# Schematic.net
KiCad netlist of a schematic drawn in Altium Designer
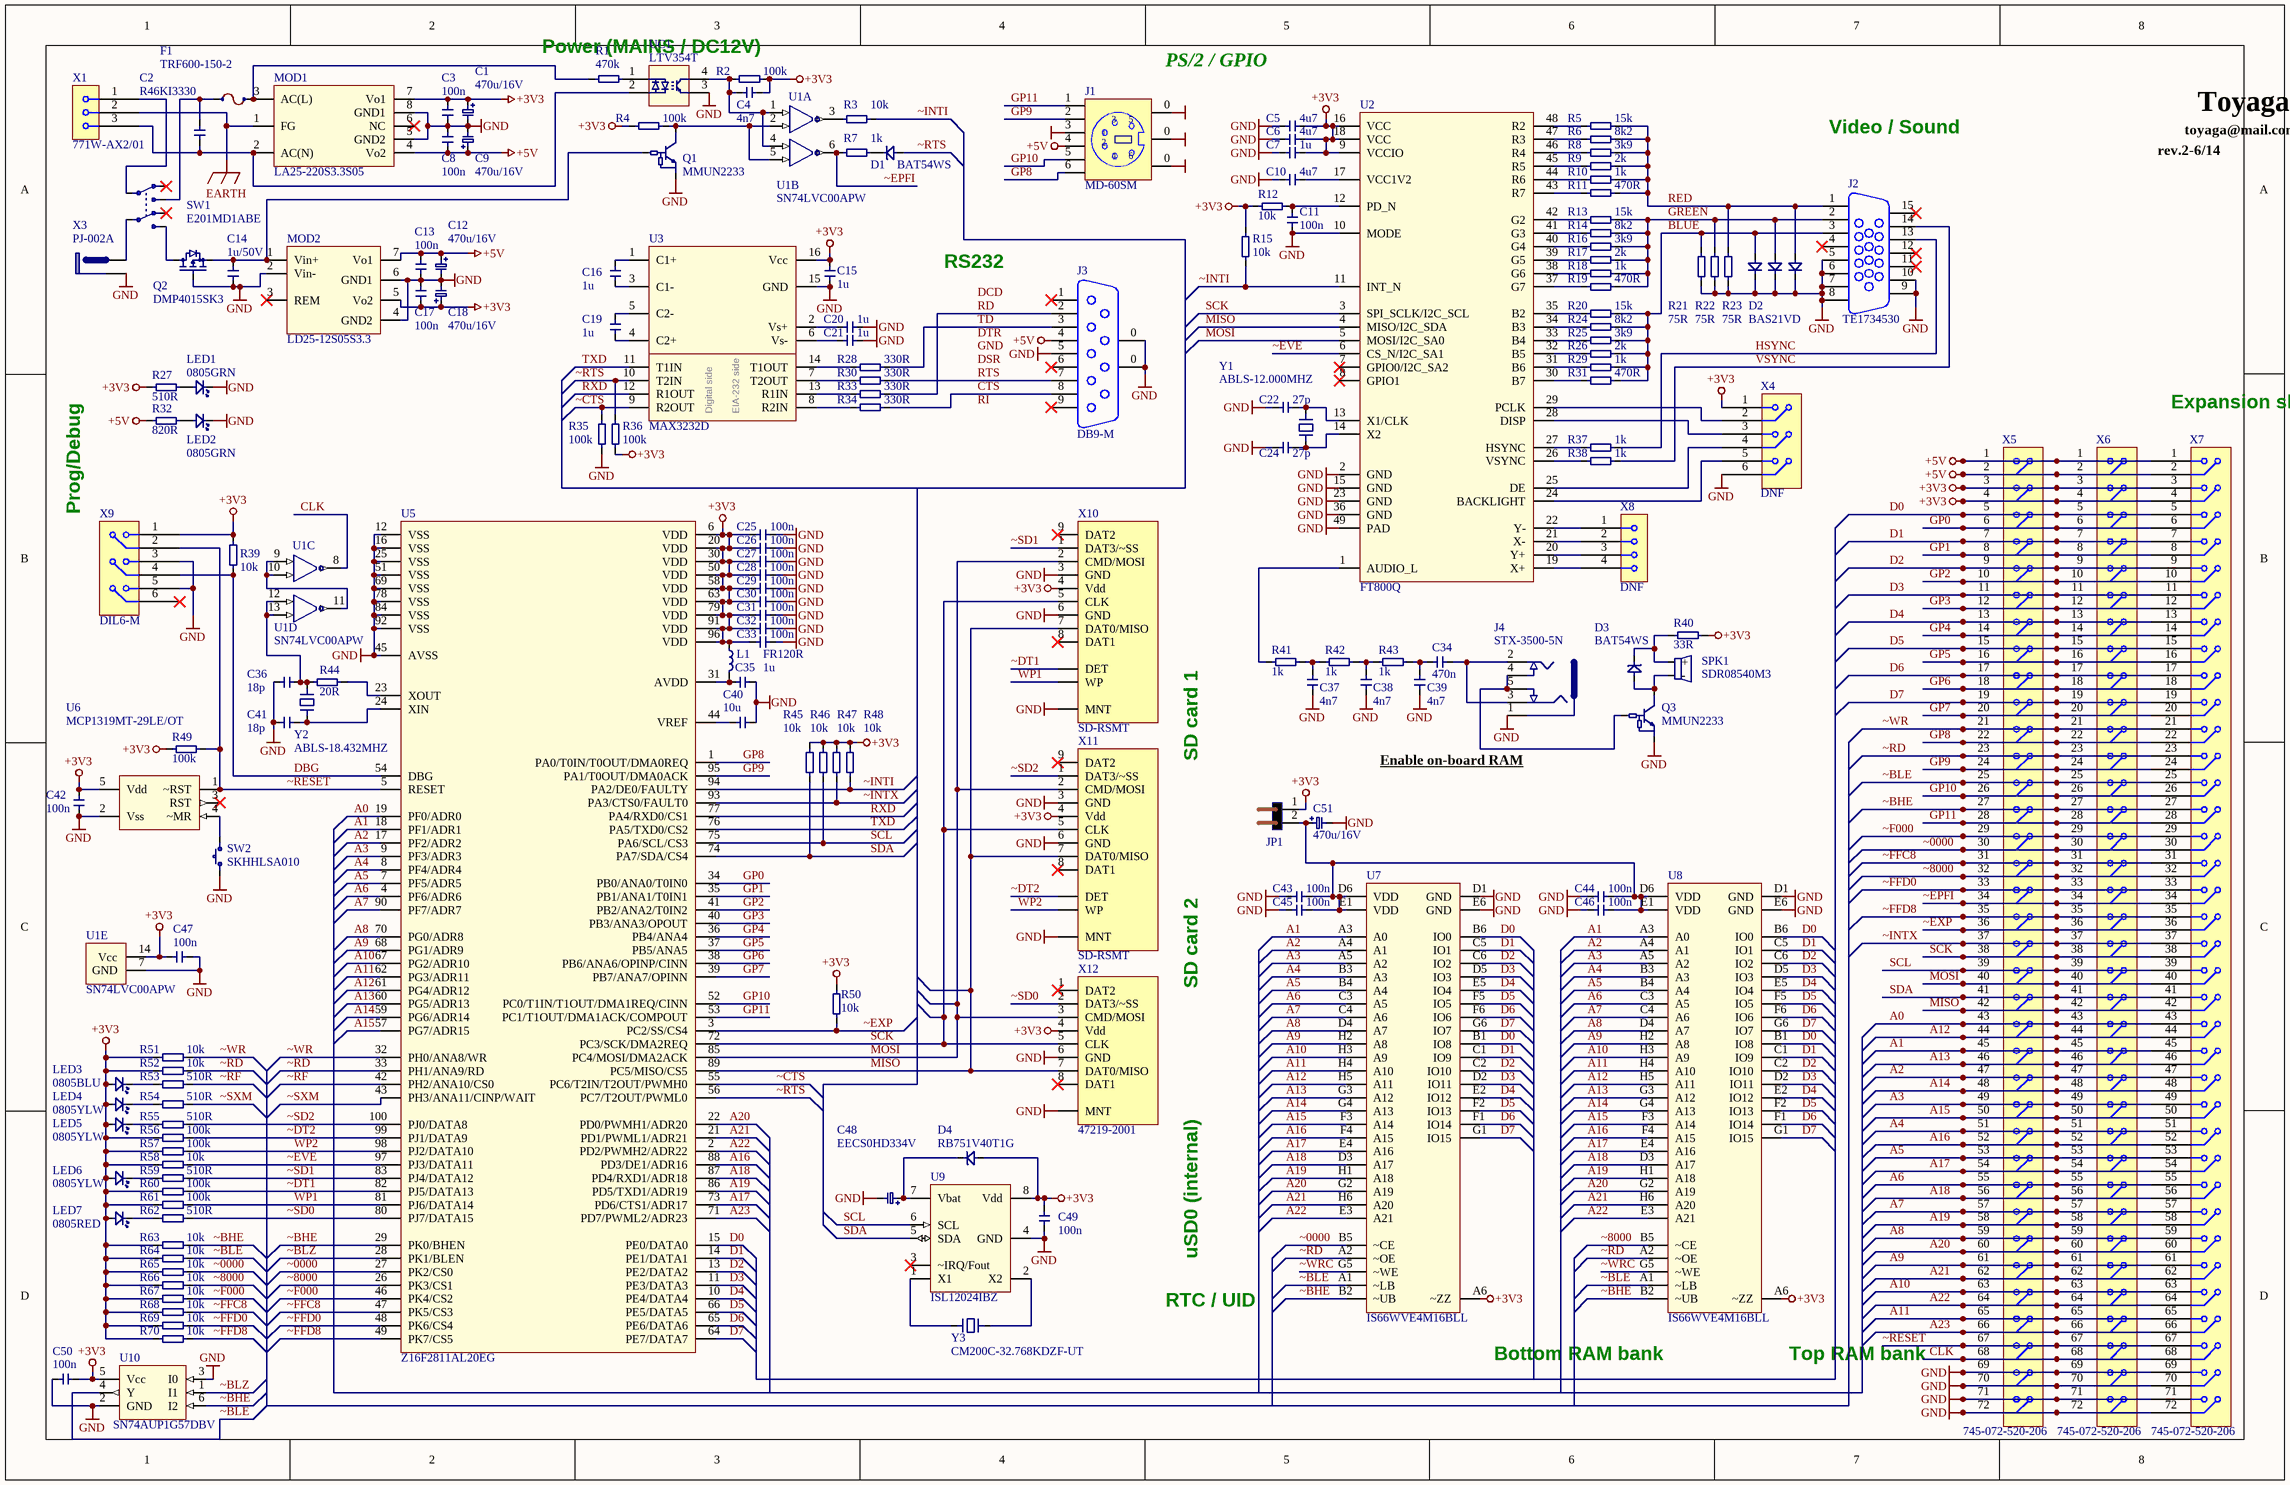
[diagram p0: Schematic.SchDoc]

(export (version "E")
  (design (tool "Eeschema 10.0.6"))
  (components
    (comp (ref "C1")
      (value "470u/16V")
      (footprint "8.5 x 8.5")
      (description "Polar capacitor")
      (libsource (lib "Discretes") (part "Capacitor+"))
    )
    (comp (ref "C2")
      (value "R46KI3330")
      (footprint "X2_15MM")
      (description "Capacitor")
      (libsource (lib "Discretes") (part "Capacitor"))
    )
    (comp (ref "C3")
      (value "100n")
      (footprint "_0805")
      (description "Capacitor")
      (libsource (lib "Discretes") (part "Capacitor"))
    )
    (comp (ref "C4")
      (value "4n7")
      (footprint "_0805")
      (description "Capacitor")
      (libsource (lib "Discretes") (part "Capacitor"))
    )
    (comp (ref "C5")
      (value "4u7")
      (footprint "_0805")
      (description "Capacitor")
      (libsource (lib "Discretes") (part "Capacitor"))
    )
    (comp (ref "C6")
      (value "4u7")
      (footprint "_0805")
      (description "Capacitor")
      (libsource (lib "Discretes") (part "Capacitor"))
    )
    (comp (ref "C7")
      (value "1u")
      (footprint "_0805")
      (description "Capacitor")
      (libsource (lib "Discretes") (part "Capacitor"))
    )
    (comp (ref "C8")
      (value "100n")
      (footprint "_0805")
      (description "Capacitor")
      (libsource (lib "Discretes") (part "Capacitor"))
    )
    (comp (ref "C9")
      (value "470u/16V")
      (footprint "8.5 x 8.5")
      (description "Polar capacitor")
      (libsource (lib "Discretes") (part "Capacitor+"))
    )
    (comp (ref "C10")
      (value "4u7")
      (footprint "_0805")
      (description "Capacitor")
      (libsource (lib "Discretes") (part "Capacitor"))
    )
    (comp (ref "C11")
      (value "100n")
      (footprint "_0805")
      (description "Capacitor")
      (libsource (lib "Discretes") (part "Capacitor"))
    )
    (comp (ref "C12")
      (value "470u/16V")
      (footprint "8.5 x 8.5")
      (description "Polar capacitor")
      (libsource (lib "Discretes") (part "Capacitor+"))
    )
    (comp (ref "C13")
      (value "100n")
      (footprint "_0805")
      (description "Capacitor")
      (libsource (lib "Discretes") (part "Capacitor"))
    )
    (comp (ref "C14")
      (value "1u/50V")
      (footprint "_1206")
      (description "Capacitor")
      (libsource (lib "Discretes") (part "Capacitor"))
    )
    (comp (ref "C15")
      (value "1u")
      (footprint "_0805")
      (description "Capacitor")
      (libsource (lib "Discretes") (part "Capacitor"))
    )
    (comp (ref "C16")
      (value "1u")
      (footprint "_0805")
      (description "Capacitor")
      (libsource (lib "Discretes") (part "Capacitor"))
    )
    (comp (ref "C17")
      (value "100n")
      (footprint "_0805")
      (description "Capacitor")
      (libsource (lib "Discretes") (part "Capacitor"))
    )
    (comp (ref "C18")
      (value "470u/16V")
      (footprint "8.5 x 8.5")
      (description "Polar capacitor")
      (libsource (lib "Discretes") (part "Capacitor+"))
    )
    (comp (ref "C19")
      (value "1u")
      (footprint "_0805")
      (description "Capacitor")
      (libsource (lib "Discretes") (part "Capacitor"))
    )
    (comp (ref "C20")
      (value "1u")
      (footprint "_0805")
      (description "Capacitor")
      (libsource (lib "Discretes") (part "Capacitor"))
    )
    (comp (ref "C21")
      (value "1u")
      (footprint "_0805")
      (description "Capacitor")
      (libsource (lib "Discretes") (part "Capacitor"))
    )
    (comp (ref "C22")
      (value "27p")
      (footprint "_0805")
      (description "Capacitor")
      (libsource (lib "Discretes") (part "Capacitor"))
    )
    (comp (ref "C24")
      (value "27p")
      (footprint "_0805")
      (description "Capacitor")
      (libsource (lib "Discretes") (part "Capacitor"))
    )
    (comp (ref "C25")
      (value "100n")
      (footprint "_0805")
      (description "Capacitor")
      (libsource (lib "Discretes") (part "Capacitor"))
    )
    (comp (ref "C26")
      (value "100n")
      (footprint "_0805")
      (description "Capacitor")
      (libsource (lib "Discretes") (part "Capacitor"))
    )
    (comp (ref "C27")
      (value "100n")
      (footprint "_0805")
      (description "Capacitor")
      (libsource (lib "Discretes") (part "Capacitor"))
    )
    (comp (ref "C28")
      (value "100n")
      (footprint "_0805")
      (description "Capacitor")
      (libsource (lib "Discretes") (part "Capacitor"))
    )
    (comp (ref "C29")
      (value "100n")
      (footprint "_0805")
      (description "Capacitor")
      (libsource (lib "Discretes") (part "Capacitor"))
    )
    (comp (ref "C30")
      (value "100n")
      (footprint "_0805")
      (description "Capacitor")
      (libsource (lib "Discretes") (part "Capacitor"))
    )
    (comp (ref "C31")
      (value "100n")
      (footprint "_0805")
      (description "Capacitor")
      (libsource (lib "Discretes") (part "Capacitor"))
    )
    (comp (ref "C32")
      (value "100n")
      (footprint "_0805")
      (description "Capacitor")
      (libsource (lib "Discretes") (part "Capacitor"))
    )
    (comp (ref "C33")
      (value "100n")
      (footprint "_0805")
      (description "Capacitor")
      (libsource (lib "Discretes") (part "Capacitor"))
    )
    (comp (ref "C34")
      (value "470n")
      (footprint "_0805")
      (description "Capacitor")
      (libsource (lib "Discretes") (part "Capacitor"))
    )
    (comp (ref "C35")
      (value "1u")
      (footprint "_0805")
      (description "Capacitor")
      (libsource (lib "Discretes") (part "Capacitor"))
    )
    (comp (ref "C36")
      (value "18p")
      (footprint "_0805")
      (description "Capacitor")
      (libsource (lib "Discretes") (part "Capacitor"))
    )
    (comp (ref "C37")
      (value "4n7")
      (footprint "_0805")
      (description "Capacitor")
      (libsource (lib "Discretes") (part "Capacitor"))
    )
    (comp (ref "C38")
      (value "4n7")
      (footprint "_0805")
      (description "Capacitor")
      (libsource (lib "Discretes") (part "Capacitor"))
    )
    (comp (ref "C39")
      (value "4n7")
      (footprint "_0805")
      (description "Capacitor")
      (libsource (lib "Discretes") (part "Capacitor"))
    )
    (comp (ref "C40")
      (value "10u")
      (footprint "_0805")
      (description "Capacitor")
      (libsource (lib "Discretes") (part "Capacitor"))
    )
    (comp (ref "C41")
      (value "18p")
      (footprint "_0805")
      (description "Capacitor")
      (libsource (lib "Discretes") (part "Capacitor"))
    )
    (comp (ref "C42")
      (value "100n")
      (footprint "_0805")
      (description "Capacitor")
      (libsource (lib "Discretes") (part "Capacitor"))
    )
    (comp (ref "C43")
      (value "100n")
      (footprint "_0805")
      (description "Capacitor")
      (libsource (lib "Discretes") (part "Capacitor"))
    )
    (comp (ref "C44")
      (value "100n")
      (footprint "_0805")
      (description "Capacitor")
      (libsource (lib "Discretes") (part "Capacitor"))
    )
    (comp (ref "C45")
      (value "100n")
      (footprint "_0805")
      (description "Capacitor")
      (libsource (lib "Discretes") (part "Capacitor"))
    )
    (comp (ref "C46")
      (value "100n")
      (footprint "_0805")
      (description "Capacitor")
      (libsource (lib "Discretes") (part "Capacitor"))
    )
    (comp (ref "C47")
      (value "100n")
      (footprint "_0805")
      (description "Capacitor")
      (libsource (lib "Discretes") (part "Capacitor"))
    )
    (comp (ref "C48")
      (value "EECS0HD334V")
      (footprint "D10.5 x L5.5")
      (description "Polar capacitor")
      (libsource (lib "Discretes") (part "Capacitor+"))
    )
    (comp (ref "C49")
      (value "100n")
      (footprint "_0805")
      (description "Capacitor")
      (libsource (lib "Discretes") (part "Capacitor"))
    )
    (comp (ref "C50")
      (value "100n")
      (footprint "_0805")
      (description "Capacitor")
      (libsource (lib "Discretes") (part "Capacitor"))
    )
    (comp (ref "C51")
      (value "470u/16V")
      (footprint "8.5 x 8.5")
      (description "Polar capacitor")
      (libsource (lib "Discretes") (part "Capacitor+"))
    )
    (comp (ref "D1")
      (value "BAT54WS")
      (footprint "SOD-323 (MicroMELF)")
      (description "Schottky diode")
      (libsource (lib "Discretes") (part "Diode Schottky"))
    )
    (comp (ref "D2")
      (value "BAS21VD")
      (footprint "SOT23-6")
      (description "Diode (triple)")
      (libsource (lib "Discretes") (part "Diode Triple"))
    )
    (comp (ref "D3")
      (value "BAT54WS")
      (footprint "SOD-323 (MicroMELF)")
      (description "Schottky diode")
      (libsource (lib "Discretes") (part "Diode Schottky"))
    )
    (comp (ref "D4")
      (value "RB751V40T1G")
      (footprint "SOD-323 (MicroMELF)")
      (description "Schottky diode")
      (libsource (lib "Discretes") (part "Diode Schottky"))
    )
    (comp (ref "F1")
      (value "TRF600-150-2")
      (footprint "Fuse 5.1mm pitch")
      (libsource (lib "Discretes") (part "Fuse Resettable"))
    )
    (comp (ref "J1")
      (value "MD-60SM")
      (footprint "MD-60SM")
      (description "6-pin mini-DIN connector (female) PS/2")
      (libsource (lib "Connectors") (part "MD-60SM"))
    )
    (comp (ref "J2")
      (value "TE1734530")
      (footprint "DB15F R/A VGA")
      (description "DB15 (3 rows) connector R/A")
      (libsource (lib "Connectors") (part "DB15 (3 rows)"))
    )
    (comp (ref "J3")
      (value "DB9-M")
      (footprint "DB9M R/A")
      (description "DB9 connector")
      (libsource (lib "Connectors") (part "DB9"))
    )
    (comp (ref "J4")
      (value "STX-3500-5N")
      (footprint "STX-3500")
      (description "Phono Jack (stereo)")
      (libsource (lib "Connectors") (part "Phono Jack Stereo (switchless)"))
    )
    (comp (ref "JP1")
      (value "SIL2-M")
      (footprint "2011-1X02S")
      (description "2.54mm square pin header/jumper")
      (libsource (lib "Connectors") (part "Jumper 2"))
    )
    (comp (ref "L1")
      (value "FR120R")
      (footprint "_0805")
      (description "Inductor")
      (libsource (lib "Discretes") (part "Inductor"))
    )
    (comp (ref "LED1")
      (value "0805GRN")
      (footprint "_0805+")
      (description "Light Emitting Diode")
      (libsource (lib "Discretes") (part "LED"))
    )
    (comp (ref "LED2")
      (value "0805GRN")
      (footprint "_0805+")
      (description "Light Emitting Diode")
      (libsource (lib "Discretes") (part "LED"))
    )
    (comp (ref "LED3")
      (value "0805BLU")
      (footprint "_0805+")
      (description "Light Emitting Diode")
      (libsource (lib "Discretes") (part "LED"))
    )
    (comp (ref "LED4")
      (value "0805YLW")
      (footprint "_0805+")
      (description "Light Emitting Diode")
      (libsource (lib "Discretes") (part "LED"))
    )
    (comp (ref "LED5")
      (value "0805YLW")
      (footprint "_0805+")
      (description "Light Emitting Diode")
      (libsource (lib "Discretes") (part "LED"))
    )
    (comp (ref "LED6")
      (value "0805YLW")
      (footprint "_0805+")
      (description "Light Emitting Diode")
      (libsource (lib "Discretes") (part "LED"))
    )
    (comp (ref "LED7")
      (value "0805RED")
      (footprint "_0805+")
      (description "Light Emitting Diode")
      (libsource (lib "Discretes") (part "LED"))
    )
    (comp (ref "MOD1")
      (value "LA25-220S3.3S05")
      (footprint "ECCO AC-DC (70x48)")
      (description "Miniature AC/DC module")
      (fields (field (name "MANUFACTURER") "ECCO"))
      (libsource (lib "16Z") (part "ECCO AC-DC dual"))
    )
    (comp (ref "MOD2")
      (value "LD25-12S05S3.3")
      (footprint "DC-DC (50.8x50.8)")
      (description "DC-DC converter isolated output with common ground and control")
      (libsource (lib "16Z") (part "ECCO DC-DC dual"))
    )
    (comp (ref "Q1")
      (value "MMUN2233")
      (footprint "SOT23-3")
      (description "NPN biased bipolar transistor")
      (libsource (lib "Discretes") (part "NPN BIASED"))
    )
    (comp (ref "Q2")
      (value "DMP4015SK3")
      (footprint "TO252-3N")
      (description "P-channel FET transistor")
      (libsource (lib "Discretes") (part "P-FET"))
    )
    (comp (ref "Q3")
      (value "MMUN2233")
      (footprint "SOT23-3")
      (description "NPN biased bipolar transistor")
      (libsource (lib "Discretes") (part "NPN BIASED"))
    )
    (comp (ref "R1")
      (value "470k")
      (footprint "_0805")
      (description "Resistor")
      (libsource (lib "") (part "Resistor_1"))
    )
    (comp (ref "R2")
      (value "100k")
      (footprint "_0805")
      (description "Resistor")
      (libsource (lib "") (part "Resistor_1"))
    )
    (comp (ref "R3")
      (value "10k")
      (footprint "_0805")
      (description "Resistor")
      (libsource (lib "") (part "Resistor_1"))
    )
    (comp (ref "R4")
      (value "100k")
      (footprint "_0805")
      (description "Resistor")
      (libsource (lib "") (part "Resistor_1"))
    )
    (comp (ref "R5")
      (value "15k")
      (footprint "_0805")
      (description "Resistor")
      (libsource (lib "") (part "Resistor_1"))
    )
    (comp (ref "R6")
      (value "8k2")
      (footprint "_0805")
      (description "Resistor")
      (libsource (lib "") (part "Resistor_1"))
    )
    (comp (ref "R7")
      (value "1k")
      (footprint "_0805")
      (description "Resistor")
      (libsource (lib "") (part "Resistor_1"))
    )
    (comp (ref "R8")
      (value "3k9")
      (footprint "_0805")
      (description "Resistor")
      (libsource (lib "") (part "Resistor_1"))
    )
    (comp (ref "R9")
      (value "2k")
      (footprint "_0805")
      (description "Resistor")
      (libsource (lib "") (part "Resistor_1"))
    )
    (comp (ref "R10")
      (value "1k")
      (footprint "_0805")
      (description "Resistor")
      (libsource (lib "") (part "Resistor_1"))
    )
    (comp (ref "R11")
      (value "470R")
      (footprint "_0805")
      (description "Resistor")
      (libsource (lib "") (part "Resistor_1"))
    )
    (comp (ref "R12")
      (value "10k")
      (footprint "_0805")
      (description "Resistor")
      (libsource (lib "") (part "Resistor_1"))
    )
    (comp (ref "R13")
      (value "15k")
      (footprint "_0805")
      (description "Resistor")
      (libsource (lib "") (part "Resistor_1"))
    )
    (comp (ref "R14")
      (value "8k2")
      (footprint "_0805")
      (description "Resistor")
      (libsource (lib "") (part "Resistor_1"))
    )
    (comp (ref "R15")
      (value "10k")
      (footprint "_0805")
      (description "Resistor")
      (libsource (lib "") (part "Resistor_2"))
    )
    (comp (ref "R16")
      (value "3k9")
      (footprint "_0805")
      (description "Resistor")
      (libsource (lib "") (part "Resistor_1"))
    )
    (comp (ref "R17")
      (value "2k")
      (footprint "_0805")
      (description "Resistor")
      (libsource (lib "") (part "Resistor_1"))
    )
    (comp (ref "R18")
      (value "1k")
      (footprint "_0805")
      (description "Resistor")
      (libsource (lib "") (part "Resistor_1"))
    )
    (comp (ref "R19")
      (value "470R")
      (footprint "_0805")
      (description "Resistor")
      (libsource (lib "") (part "Resistor_1"))
    )
    (comp (ref "R20")
      (value "15k")
      (footprint "_0805")
      (description "Resistor")
      (libsource (lib "") (part "Resistor_1"))
    )
    (comp (ref "R21")
      (value "75R")
      (footprint "_0805")
      (description "Resistor")
      (libsource (lib "") (part "Resistor_2"))
    )
    (comp (ref "R22")
      (value "75R")
      (footprint "_0805")
      (description "Resistor")
      (libsource (lib "") (part "Resistor_2"))
    )
    (comp (ref "R23")
      (value "75R")
      (footprint "_0805")
      (description "Resistor")
      (libsource (lib "") (part "Resistor_2"))
    )
    (comp (ref "R24")
      (value "8k2")
      (footprint "_0805")
      (description "Resistor")
      (libsource (lib "") (part "Resistor_1"))
    )
    (comp (ref "R25")
      (value "3k9")
      (footprint "_0805")
      (description "Resistor")
      (libsource (lib "") (part "Resistor_1"))
    )
    (comp (ref "R26")
      (value "2k")
      (footprint "_0805")
      (description "Resistor")
      (libsource (lib "") (part "Resistor_1"))
    )
    (comp (ref "R27")
      (value "510R")
      (footprint "_0805")
      (description "Resistor")
      (libsource (lib "Discretes") (part "Resistor"))
    )
    (comp (ref "R28")
      (value "330R")
      (footprint "_0805")
      (description "Resistor")
      (libsource (lib "") (part "Resistor_1"))
    )
    (comp (ref "R29")
      (value "1k")
      (footprint "_0805")
      (description "Resistor")
      (libsource (lib "") (part "Resistor_1"))
    )
    (comp (ref "R30")
      (value "330R")
      (footprint "_0805")
      (description "Resistor")
      (libsource (lib "") (part "Resistor_1"))
    )
    (comp (ref "R31")
      (value "470R")
      (footprint "_0805")
      (description "Resistor")
      (libsource (lib "") (part "Resistor_1"))
    )
    (comp (ref "R32")
      (value "820R")
      (footprint "_0805")
      (description "Resistor")
      (libsource (lib "Discretes") (part "Resistor"))
    )
    (comp (ref "R33")
      (value "330R")
      (footprint "_0805")
      (description "Resistor")
      (libsource (lib "") (part "Resistor_1"))
    )
    (comp (ref "R34")
      (value "330R")
      (footprint "_0805")
      (description "Resistor")
      (libsource (lib "") (part "Resistor_1"))
    )
    (comp (ref "R35")
      (value "100k")
      (footprint "_0805")
      (description "Resistor")
      (libsource (lib "") (part "Resistor_2"))
    )
    (comp (ref "R36")
      (value "100k")
      (footprint "_0805")
      (description "Resistor")
      (libsource (lib "") (part "Resistor_2"))
    )
    (comp (ref "R37")
      (value "1k")
      (footprint "_0805")
      (description "Resistor")
      (libsource (lib "") (part "Resistor_1"))
    )
    (comp (ref "R38")
      (value "1k")
      (footprint "_0805")
      (description "Resistor")
      (libsource (lib "") (part "Resistor_1"))
    )
    (comp (ref "R39")
      (value "10k")
      (footprint "_0805")
      (description "Resistor")
      (libsource (lib "") (part "Resistor_3"))
    )
    (comp (ref "R40")
      (value "33R")
      (footprint "_0805")
      (description "Resistor")
      (libsource (lib "") (part "Resistor_1"))
    )
    (comp (ref "R41")
      (value "1k")
      (footprint "_0805")
      (description "Resistor")
      (libsource (lib "") (part "Resistor_1"))
    )
    (comp (ref "R42")
      (value "1k")
      (footprint "_0805")
      (description "Resistor")
      (libsource (lib "") (part "Resistor_1"))
    )
    (comp (ref "R43")
      (value "1k")
      (footprint "_0805")
      (description "Resistor")
      (libsource (lib "") (part "Resistor_1"))
    )
    (comp (ref "R44")
      (value "20R")
      (footprint "_0805")
      (description "Resistor")
      (libsource (lib "Discretes") (part "Resistor"))
    )
    (comp (ref "R45")
      (value "10k")
      (footprint "_0805")
      (description "Resistor")
      (libsource (lib "") (part "Resistor_2"))
    )
    (comp (ref "R46")
      (value "10k")
      (footprint "_0805")
      (description "Resistor")
      (libsource (lib "") (part "Resistor_2"))
    )
    (comp (ref "R47")
      (value "10k")
      (footprint "_0805")
      (description "Resistor")
      (libsource (lib "") (part "Resistor_2"))
    )
    (comp (ref "R48")
      (value "10k")
      (footprint "_0805")
      (description "Resistor")
      (libsource (lib "") (part "Resistor_2"))
    )
    (comp (ref "R49")
      (value "100k")
      (footprint "_0805")
      (description "Resistor")
      (libsource (lib "Discretes") (part "Resistor"))
    )
    (comp (ref "R50")
      (value "10k")
      (footprint "_0805")
      (description "Resistor")
      (libsource (lib "") (part "Resistor_2"))
    )
    (comp (ref "R51")
      (value "10k")
      (footprint "_0805")
      (description "Resistor")
      (libsource (lib "Discretes") (part "Resistor"))
    )
    (comp (ref "R52")
      (value "10k")
      (footprint "_0805")
      (description "Resistor")
      (libsource (lib "Discretes") (part "Resistor"))
    )
    (comp (ref "R53")
      (value "510R")
      (footprint "_0805")
      (description "Resistor")
      (libsource (lib "Discretes") (part "Resistor"))
    )
    (comp (ref "R54")
      (value "510R")
      (footprint "_0805")
      (description "Resistor")
      (libsource (lib "Discretes") (part "Resistor"))
    )
    (comp (ref "R55")
      (value "510R")
      (footprint "_0805")
      (description "Resistor")
      (libsource (lib "Discretes") (part "Resistor"))
    )
    (comp (ref "R56")
      (value "100k")
      (footprint "_0805")
      (description "Resistor")
      (libsource (lib "Discretes") (part "Resistor"))
    )
    (comp (ref "R57")
      (value "100k")
      (footprint "_0805")
      (description "Resistor")
      (libsource (lib "Discretes") (part "Resistor"))
    )
    (comp (ref "R58")
      (value "10k")
      (footprint "_0805")
      (description "Resistor")
      (libsource (lib "Discretes") (part "Resistor"))
    )
    (comp (ref "R59")
      (value "510R")
      (footprint "_0805")
      (description "Resistor")
      (libsource (lib "Discretes") (part "Resistor"))
    )
    (comp (ref "R60")
      (value "100k")
      (footprint "_0805")
      (description "Resistor")
      (libsource (lib "Discretes") (part "Resistor"))
    )
    (comp (ref "R61")
      (value "100k")
      (footprint "_0805")
      (description "Resistor")
      (libsource (lib "Discretes") (part "Resistor"))
    )
    (comp (ref "R62")
      (value "510R")
      (footprint "_0805")
      (description "Resistor")
      (libsource (lib "Discretes") (part "Resistor"))
    )
    (comp (ref "R63")
      (value "10k")
      (footprint "_0805")
      (description "Resistor")
      (libsource (lib "Discretes") (part "Resistor"))
    )
    (comp (ref "R64")
      (value "10k")
      (footprint "_0805")
      (description "Resistor")
      (libsource (lib "Discretes") (part "Resistor"))
    )
    (comp (ref "R65")
      (value "10k")
      (footprint "_0805")
      (description "Resistor")
      (libsource (lib "Discretes") (part "Resistor"))
    )
    (comp (ref "R66")
      (value "10k")
      (footprint "_0805")
      (description "Resistor")
      (libsource (lib "Discretes") (part "Resistor"))
    )
    (comp (ref "R67")
      (value "10k")
      (footprint "_0805")
      (description "Resistor")
      (libsource (lib "Discretes") (part "Resistor"))
    )
    (comp (ref "R68")
      (value "10k")
      (footprint "_0805")
      (description "Resistor")
      (libsource (lib "Discretes") (part "Resistor"))
    )
    (comp (ref "R69")
      (value "10k")
      (footprint "_0805")
      (description "Resistor")
      (libsource (lib "Discretes") (part "Resistor"))
    )
    (comp (ref "R70")
      (value "10k")
      (footprint "_0805")
      (description "Resistor")
      (libsource (lib "Discretes") (part "Resistor"))
    )
    (comp (ref "SPK1")
      (value "SDR08540M3")
      (footprint "SDR08540M3-01")
      (description "Speaker/Buzzer")
      (libsource (lib "Discretes") (part "Speaker"))
    )
    (comp (ref "SW1")
      (value "E201MD1ABE")
      (footprint "E201MD1ABE")
      (description "Switch")
      (libsource (lib "Switches") (part "Switch DPDT"))
    )
    (comp (ref "SW2")
      (value "SKHHLSA010")
      (footprint "SKHH-HORIZONTAL")
      (description "Switch, Momentary, Normal Open")
      (libsource (lib "Switches") (part "Switch MNO SPST"))
    )
    (comp (ref "U1")
      (value "SN74LVC00APW")
      (footprint "TSOP65P640-14N")
      (description "Quad NAND")
      (libsource (lib "IC Logic") (part "74xxx00"))
    )
    (comp (ref "U2")
      (value "FT800Q")
      (footprint "QFN50P700X700-48W2N")
      (description "Embedded Video Engine")
      (fields (field (name "MANUFACTURER") "FTDI"))
      (libsource (lib "IC Audio and Video") (part "FT800Q"))
    )
    (comp (ref "U3")
      (value "MAX3232D")
      (footprint "SOIC16")
      (description "Dual EIA-232 drivers")
      (fields (field (name "MANUFACTURER") "TI (and others)"))
      (libsource (lib "IC Interface") (part "MAX232"))
    )
    (comp (ref "U5")
      (value "Z16F2811AL20EG")
      (footprint "LQFP100")
      (description "16-bit microcontroller/microprocessor")
      (fields (field (name "MANUFACTURER") "Zilog"))
      (libsource (lib "IC Microcontrollers and Processors") (part "Z16F (QFP100)"))
    )
    (comp (ref "U6")
      (value "MCP1319MT-29LE/OT")
      (footprint "SOT23-5")
      (description "Voltage Supervisor")
      (fields (field (name "MANUFACTURER") "Microchip"))
      (libsource (lib "IC Other Functions") (part "MCP1319"))
    )
    (comp (ref "U7")
      (value "IS66WVE4M16BLL")
      (footprint "BGA75P6X8-48")
      (description "4M x 16 high speed asynchronous pseudostatic RAM")
      (libsource (lib "IC Other Functions") (part "IS66WVE4M16 BGA"))
    )
    (comp (ref "U8")
      (value "IS66WVE4M16BLL")
      (footprint "BGA75P6X8-48")
      (description "4M x 16 high speed asynchronous pseudostatic RAM")
      (libsource (lib "IC Other Functions") (part "IS66WVE4M16 BGA"))
    )
    (comp (ref "U9")
      (value "ISL12024IBZ")
      (footprint "SOIC8")
      (description "Real-Time Clock/Calendar with Embedded  Unique ID")
      (fields (field (name "MANUFACTURER") "Intersil"))
      (libsource (lib "IC Other Functions") (part "ISL12024"))
    )
    (comp (ref "U10")
      (value "SN74AUP1G57DBV")
      (footprint "SOT23-6")
      (description "Universal logic element")
      (fields (field (name "MANUFACTURER") "Texas Instruments"))
      (libsource (lib "IC Logic") (part "SN74AUP1G57"))
    )
    (comp (ref "UC1")
      (value "LTV354T")
      (footprint "SO4")
      (description "Optocoupler AC")
      (libsource (lib "Discretes") (part "OPTO AC"))
    )
    (comp (ref "X1")
      (value "771W-AX2/01")
      (footprint "771W-AX2/01")
      (description "Single row, 3-way connector")
      (libsource (lib "Connectors") (part "Connector 1x3"))
    )
    (comp (ref "X3")
      (value "PJ-002A")
      (footprint "KLD-0202")
      (description "Power Jack 2.1mm or 2.5mm")
      (libsource (lib "Connectors") (part "Power Jack 2.5"))
    )
    (comp (ref "X4")
      (value "DNF")
      (footprint "2011-2X03S")
      (description "Dual row, 6-way connector")
      (libsource (lib "Connectors") (part "Connector 2x3"))
    )
    (comp (ref "X5")
      (value "745-072-520-206")
      (footprint "745-072-520-206")
      (description "Dual row, 72-way connector")
      (libsource (lib "Connectors") (part "Connector 2x36"))
    )
    (comp (ref "X6")
      (value "745-072-520-206")
      (footprint "745-072-520-206")
      (description "Dual row, 72-way connector")
      (libsource (lib "Connectors") (part "Connector 2x36"))
    )
    (comp (ref "X7")
      (value "745-072-520-206")
      (footprint "745-072-520-206")
      (description "Dual row, 72-way connector")
      (libsource (lib "Connectors") (part "Connector 2x36"))
    )
    (comp (ref "X8")
      (value "DNF")
      (footprint "2011-1X04S")
      (description "Single row, 4-way connector")
      (libsource (lib "Connectors") (part "Connector 1x4"))
    )
    (comp (ref "X9")
      (value "DIL6-M")
      (footprint "2011-2X03S")
      (description "Dual row, 6-way connector")
      (libsource (lib "") (part "Connector 2x3_1"))
    )
    (comp (ref "X10")
      (value "SD-RSMT")
      (footprint "SD-RSMT")
      (description "SD card connector")
      (libsource (lib "Connectors") (part "SD (w/ card detect and WP)"))
    )
    (comp (ref "X11")
      (value "SD-RSMT")
      (footprint "SD-RSMT")
      (description "SD card connector")
      (libsource (lib "Connectors") (part "SD (w/ card detect and WP)"))
    )
    (comp (ref "X12")
      (value "47219-2001")
      (footprint "MOLEX_47219-2001")
      (description "microSD card connector")
      (libsource (lib "Connectors") (part "microSD"))
    )
    (comp (ref "Y1")
      (value "ABLS-12.000MHZ")
      (footprint "HC49/SMT")
      (description "Crystal Resonator")
      (libsource (lib "Discretes") (part "Crystal"))
    )
    (comp (ref "Y2")
      (value "ABLS-18.432MHZ")
      (footprint "HC49/SMT")
      (description "Crystal Resonator")
      (libsource (lib "Discretes") (part "Crystal"))
    )
    (comp (ref "Y3")
      (value "CM200C-32.768KDZF-UT")
      (footprint "Crystal 79X37 (4)")
      (description "Crystal Resonator")
      (libsource (lib "") (part "Crystal_1"))
    )
  )
  (nets
    (net (code "1") (name "+3V3") (class "Default")
      (node (ref "C1") (pin "1") (pintype "passive"))
      (node (ref "C15") (pin "1") (pintype "passive"))
      (node (ref "C17") (pin "2") (pintype "passive"))
      (node (ref "C18") (pin "1") (pintype "passive"))
      (node (ref "C25") (pin "2") (pintype "passive"))
      (node (ref "C26") (pin "2") (pintype "passive"))
      (node (ref "C27") (pin "2") (pintype "passive"))
      (node (ref "C28") (pin "2") (pintype "passive"))
      (node (ref "C29") (pin "2") (pintype "passive"))
      (node (ref "C3") (pin "2") (pintype "passive"))
      (node (ref "C30") (pin "2") (pintype "passive"))
      (node (ref "C31") (pin "2") (pintype "passive"))
      (node (ref "C32") (pin "2") (pintype "passive"))
      (node (ref "C33") (pin "2") (pintype "passive"))
      (node (ref "C4") (pin "2") (pintype "passive"))
      (node (ref "C42") (pin "1") (pintype "passive"))
      (node (ref "C47") (pin "1") (pintype "passive"))
      (node (ref "C49") (pin "1") (pintype "passive"))
      (node (ref "C5") (pin "1") (pintype "passive"))
      (node (ref "C50") (pin "2") (pintype "passive"))
      (node (ref "C6") (pin "1") (pintype "passive"))
      (node (ref "C7") (pin "1") (pintype "passive"))
      (node (ref "D4") (pin "2") (pintype "passive"))
      (node (ref "JP1") (pin "1") (pintype "passive"))
      (node (ref "L1") (pin "2") (pintype "passive"))
      (node (ref "LED3") (pin "2") (pintype "passive"))
      (node (ref "LED4") (pin "2") (pintype "passive"))
      (node (ref "LED5") (pin "2") (pintype "passive"))
      (node (ref "LED6") (pin "2") (pintype "passive"))
      (node (ref "LED7") (pin "2") (pintype "passive"))
      (node (ref "MOD1") (pin "7") (pinfunction "Vo1_7") (pintype "power_in"))
      (node (ref "MOD2") (pin "5") (pinfunction "Vo2_5") (pintype "power_in"))
      (node (ref "R12") (pin "1") (pintype "passive"))
      (node (ref "R15") (pin "2") (pintype "passive"))
      (node (ref "R2") (pin "2") (pintype "passive"))
      (node (ref "R27") (pin "2") (pintype "passive"))
      (node (ref "R36") (pin "1") (pintype "passive"))
      (node (ref "R39") (pin "1") (pintype "passive"))
      (node (ref "R4") (pin "1") (pintype "passive"))
      (node (ref "R40") (pin "2") (pintype "passive"))
      (node (ref "R45") (pin "2") (pintype "passive"))
      (node (ref "R46") (pin "2") (pintype "passive"))
      (node (ref "R47") (pin "2") (pintype "passive"))
      (node (ref "R48") (pin "2") (pintype "passive"))
      (node (ref "R49") (pin "2") (pintype "passive"))
      (node (ref "R50") (pin "2") (pintype "passive"))
      (node (ref "R51") (pin "2") (pintype "passive"))
      (node (ref "R52") (pin "2") (pintype "passive"))
      (node (ref "R56") (pin "2") (pintype "passive"))
      (node (ref "R57") (pin "2") (pintype "passive"))
      (node (ref "R58") (pin "2") (pintype "passive"))
      (node (ref "R60") (pin "2") (pintype "passive"))
      (node (ref "R61") (pin "2") (pintype "passive"))
      (node (ref "R63") (pin "2") (pintype "passive"))
      (node (ref "R64") (pin "2") (pintype "passive"))
      (node (ref "R65") (pin "2") (pintype "passive"))
      (node (ref "R66") (pin "2") (pintype "passive"))
      (node (ref "R67") (pin "2") (pintype "passive"))
      (node (ref "R68") (pin "2") (pintype "passive"))
      (node (ref "R69") (pin "2") (pintype "passive"))
      (node (ref "R70") (pin "2") (pintype "passive"))
      (node (ref "U1") (pin "14") (pinfunction "Vcc_14") (pintype "passive"))
      (node (ref "U10") (pin "5") (pinfunction "Vcc_5") (pintype "power_in"))
      (node (ref "U2") (pin "16") (pinfunction "VCC_16") (pintype "passive"))
      (node (ref "U2") (pin "18") (pinfunction "VCC_18") (pintype "passive"))
      (node (ref "U2") (pin "9") (pinfunction "VCCIO_9") (pintype "passive"))
      (node (ref "U3") (pin "16") (pinfunction "Vcc_16") (pintype "passive"))
      (node (ref "U5") (pin "20") (pinfunction "VDD_20") (pintype "passive"))
      (node (ref "U5") (pin "30") (pinfunction "VDD_30") (pintype "passive"))
      (node (ref "U5") (pin "50") (pinfunction "VDD_50") (pintype "passive"))
      (node (ref "U5") (pin "58") (pinfunction "VDD_58") (pintype "passive"))
      (node (ref "U5") (pin "6") (pinfunction "VDD_6") (pintype "passive"))
      (node (ref "U5") (pin "63") (pinfunction "VDD_63") (pintype "passive"))
      (node (ref "U5") (pin "79") (pinfunction "VDD_79") (pintype "passive"))
      (node (ref "U5") (pin "91") (pinfunction "VDD_91") (pintype "passive"))
      (node (ref "U5") (pin "96") (pinfunction "VDD_96") (pintype "passive"))
      (node (ref "U6") (pin "5") (pinfunction "Vdd_5") (pintype "power_in"))
      (node (ref "U7") (pin "A6") (pinfunction "~ZZ_A6") (pintype "passive"))
      (node (ref "U8") (pin "A6") (pinfunction "~ZZ_A6") (pintype "passive"))
      (node (ref "U9") (pin "8") (pinfunction "Vdd_8") (pintype "power_in"))
      (node (ref "X10") (pin "4") (pinfunction "Vdd_4") (pintype "passive"))
      (node (ref "X11") (pin "4") (pinfunction "Vdd_4") (pintype "passive"))
      (node (ref "X12") (pin "4") (pinfunction "Vdd_4") (pintype "passive"))
      (node (ref "X4") (pin "1") (pinfunction "1_1") (pintype "passive"))
      (node (ref "X5") (pin "3") (pinfunction "3_3") (pintype "passive"))
      (node (ref "X5") (pin "4") (pinfunction "4_4") (pintype "passive"))
      (node (ref "X6") (pin "3") (pinfunction "3_3") (pintype "passive"))
      (node (ref "X6") (pin "4") (pinfunction "4_4") (pintype "passive"))
      (node (ref "X7") (pin "3") (pinfunction "3_3") (pintype "passive"))
      (node (ref "X7") (pin "4") (pinfunction "4_4") (pintype "passive"))
      (node (ref "X9") (pin "1") (pinfunction "1_1") (pintype "passive"))
    )
    (net (code "2") (name "+5V") (class "Default")
      (node (ref "C12") (pin "1") (pintype "passive"))
      (node (ref "C13") (pin "1") (pintype "passive"))
      (node (ref "C8") (pin "1") (pintype "passive"))
      (node (ref "C9") (pin "1") (pintype "passive"))
      (node (ref "J1") (pin "4") (pintype "passive"))
      (node (ref "J3") (pin "4") (pinfunction "4_4") (pintype "passive"))
      (node (ref "MOD1") (pin "4") (pinfunction "Vo2_4") (pintype "power_in"))
      (node (ref "MOD2") (pin "7") (pinfunction "Vo1_7") (pintype "power_in"))
      (node (ref "R32") (pin "2") (pintype "passive"))
      (node (ref "X5") (pin "1") (pinfunction "1_1") (pintype "passive"))
      (node (ref "X5") (pin "2") (pinfunction "2_2") (pintype "passive"))
      (node (ref "X6") (pin "1") (pinfunction "1_1") (pintype "passive"))
      (node (ref "X6") (pin "2") (pinfunction "2_2") (pintype "passive"))
      (node (ref "X7") (pin "1") (pinfunction "1_1") (pintype "passive"))
      (node (ref "X7") (pin "2") (pinfunction "2_2") (pintype "passive"))
    )
    (net (code "3") (name "/A0") (class "Default")
      (node (ref "U5") (pin "19") (pinfunction "PF0/ADR0_19") (pintype "passive"))
      (node (ref "X5") (pin "43") (pinfunction "43_43") (pintype "passive"))
      (node (ref "X6") (pin "43") (pinfunction "43_43") (pintype "passive"))
      (node (ref "X7") (pin "43") (pinfunction "43_43") (pintype "passive"))
    )
    (net (code "4") (name "/A1") (class "Default")
      (node (ref "U5") (pin "18") (pinfunction "PF1/ADR1_18") (pintype "passive"))
      (node (ref "U7") (pin "A3") (pinfunction "A0_A3") (pintype "passive"))
      (node (ref "U8") (pin "A3") (pinfunction "A0_A3") (pintype "passive"))
      (node (ref "X5") (pin "45") (pinfunction "45_45") (pintype "passive"))
      (node (ref "X6") (pin "45") (pinfunction "45_45") (pintype "passive"))
      (node (ref "X7") (pin "45") (pinfunction "45_45") (pintype "passive"))
    )
    (net (code "5") (name "/A2") (class "Default")
      (node (ref "U5") (pin "17") (pinfunction "PF2/ADR2_17") (pintype "passive"))
      (node (ref "U7") (pin "A4") (pinfunction "A1_A4") (pintype "passive"))
      (node (ref "U8") (pin "A4") (pinfunction "A1_A4") (pintype "passive"))
      (node (ref "X5") (pin "47") (pinfunction "47_47") (pintype "passive"))
      (node (ref "X6") (pin "47") (pinfunction "47_47") (pintype "passive"))
      (node (ref "X7") (pin "47") (pinfunction "47_47") (pintype "passive"))
    )
    (net (code "6") (name "/A3") (class "Default")
      (node (ref "U5") (pin "9") (pinfunction "PF3/ADR3_9") (pintype "passive"))
      (node (ref "U7") (pin "A5") (pinfunction "A2_A5") (pintype "passive"))
      (node (ref "U8") (pin "A5") (pinfunction "A2_A5") (pintype "passive"))
      (node (ref "X5") (pin "49") (pinfunction "49_49") (pintype "passive"))
      (node (ref "X6") (pin "49") (pinfunction "49_49") (pintype "passive"))
      (node (ref "X7") (pin "49") (pinfunction "49_49") (pintype "passive"))
    )
    (net (code "7") (name "/A4") (class "Default")
      (node (ref "U5") (pin "8") (pinfunction "PF4/ADR4_8") (pintype "passive"))
      (node (ref "U7") (pin "B3") (pinfunction "A3_B3") (pintype "passive"))
      (node (ref "U8") (pin "B3") (pinfunction "A3_B3") (pintype "passive"))
      (node (ref "X5") (pin "51") (pinfunction "51_51") (pintype "passive"))
      (node (ref "X6") (pin "51") (pinfunction "51_51") (pintype "passive"))
      (node (ref "X7") (pin "51") (pinfunction "51_51") (pintype "passive"))
    )
    (net (code "8") (name "/A5") (class "Default")
      (node (ref "U5") (pin "7") (pinfunction "PF5/ADR5_7") (pintype "passive"))
      (node (ref "U7") (pin "B4") (pinfunction "A4_B4") (pintype "passive"))
      (node (ref "U8") (pin "B4") (pinfunction "A4_B4") (pintype "passive"))
      (node (ref "X5") (pin "53") (pinfunction "53_53") (pintype "passive"))
      (node (ref "X6") (pin "53") (pinfunction "53_53") (pintype "passive"))
      (node (ref "X7") (pin "53") (pinfunction "53_53") (pintype "passive"))
    )
    (net (code "9") (name "/A6") (class "Default")
      (node (ref "U5") (pin "4") (pinfunction "PF6/ADR6_4") (pintype "passive"))
      (node (ref "U7") (pin "C3") (pinfunction "A5_C3") (pintype "passive"))
      (node (ref "U8") (pin "C3") (pinfunction "A5_C3") (pintype "passive"))
      (node (ref "X5") (pin "55") (pinfunction "55_55") (pintype "passive"))
      (node (ref "X6") (pin "55") (pinfunction "55_55") (pintype "passive"))
      (node (ref "X7") (pin "55") (pinfunction "55_55") (pintype "passive"))
    )
    (net (code "10") (name "/A7") (class "Default")
      (node (ref "U5") (pin "90") (pinfunction "PF7/ADR7_90") (pintype "passive"))
      (node (ref "U7") (pin "C4") (pinfunction "A6_C4") (pintype "passive"))
      (node (ref "U8") (pin "C4") (pinfunction "A6_C4") (pintype "passive"))
      (node (ref "X5") (pin "57") (pinfunction "57_57") (pintype "passive"))
      (node (ref "X6") (pin "57") (pinfunction "57_57") (pintype "passive"))
      (node (ref "X7") (pin "57") (pinfunction "57_57") (pintype "passive"))
    )
    (net (code "11") (name "/A8") (class "Default")
      (node (ref "U5") (pin "70") (pinfunction "PG0/ADR8_70") (pintype "passive"))
      (node (ref "U7") (pin "D4") (pinfunction "A7_D4") (pintype "passive"))
      (node (ref "U8") (pin "D4") (pinfunction "A7_D4") (pintype "passive"))
      (node (ref "X5") (pin "59") (pinfunction "59_59") (pintype "passive"))
      (node (ref "X6") (pin "59") (pinfunction "59_59") (pintype "passive"))
      (node (ref "X7") (pin "59") (pinfunction "59_59") (pintype "passive"))
    )
    (net (code "12") (name "/A9") (class "Default")
      (node (ref "U5") (pin "68") (pinfunction "PG1/ADR9_68") (pintype "passive"))
      (node (ref "U7") (pin "H2") (pinfunction "A8_H2") (pintype "passive"))
      (node (ref "U8") (pin "H2") (pinfunction "A8_H2") (pintype "passive"))
      (node (ref "X5") (pin "61") (pinfunction "61_61") (pintype "passive"))
      (node (ref "X6") (pin "61") (pinfunction "61_61") (pintype "passive"))
      (node (ref "X7") (pin "61") (pinfunction "61_61") (pintype "passive"))
    )
    (net (code "13") (name "/A10") (class "Default")
      (node (ref "U5") (pin "67") (pinfunction "PG2/ADR10_67") (pintype "passive"))
      (node (ref "U7") (pin "H3") (pinfunction "A9_H3") (pintype "passive"))
      (node (ref "U8") (pin "H3") (pinfunction "A9_H3") (pintype "passive"))
      (node (ref "X5") (pin "63") (pinfunction "63_63") (pintype "passive"))
      (node (ref "X6") (pin "63") (pinfunction "63_63") (pintype "passive"))
      (node (ref "X7") (pin "63") (pinfunction "63_63") (pintype "passive"))
    )
    (net (code "14") (name "/A11") (class "Default")
      (node (ref "U5") (pin "62") (pinfunction "PG3/ADR11_62") (pintype "passive"))
      (node (ref "U7") (pin "H4") (pinfunction "A10_H4") (pintype "passive"))
      (node (ref "U8") (pin "H4") (pinfunction "A10_H4") (pintype "passive"))
      (node (ref "X5") (pin "65") (pinfunction "65_65") (pintype "passive"))
      (node (ref "X6") (pin "65") (pinfunction "65_65") (pintype "passive"))
      (node (ref "X7") (pin "65") (pinfunction "65_65") (pintype "passive"))
    )
    (net (code "15") (name "/A12") (class "Default")
      (node (ref "U5") (pin "61") (pinfunction "PG4/ADR12_61") (pintype "passive"))
      (node (ref "U7") (pin "H5") (pinfunction "A11_H5") (pintype "passive"))
      (node (ref "U8") (pin "H5") (pinfunction "A11_H5") (pintype "passive"))
      (node (ref "X5") (pin "44") (pinfunction "44_44") (pintype "passive"))
      (node (ref "X6") (pin "44") (pinfunction "44_44") (pintype "passive"))
      (node (ref "X7") (pin "44") (pinfunction "44_44") (pintype "passive"))
    )
    (net (code "16") (name "/A13") (class "Default")
      (node (ref "U5") (pin "60") (pinfunction "PG5/ADR13_60") (pintype "passive"))
      (node (ref "U7") (pin "G3") (pinfunction "A12_G3") (pintype "passive"))
      (node (ref "U8") (pin "G3") (pinfunction "A12_G3") (pintype "passive"))
      (node (ref "X5") (pin "46") (pinfunction "46_46") (pintype "passive"))
      (node (ref "X6") (pin "46") (pinfunction "46_46") (pintype "passive"))
      (node (ref "X7") (pin "46") (pinfunction "46_46") (pintype "passive"))
    )
    (net (code "17") (name "/A14") (class "Default")
      (node (ref "U5") (pin "59") (pinfunction "PG6/ADR14_59") (pintype "passive"))
      (node (ref "U7") (pin "G4") (pinfunction "A13_G4") (pintype "passive"))
      (node (ref "U8") (pin "G4") (pinfunction "A13_G4") (pintype "passive"))
      (node (ref "X5") (pin "48") (pinfunction "48_48") (pintype "passive"))
      (node (ref "X6") (pin "48") (pinfunction "48_48") (pintype "passive"))
      (node (ref "X7") (pin "48") (pinfunction "48_48") (pintype "passive"))
    )
    (net (code "18") (name "/A15") (class "Default")
      (node (ref "U5") (pin "57") (pinfunction "PG7/ADR15_57") (pintype "passive"))
      (node (ref "U7") (pin "F3") (pinfunction "A14_F3") (pintype "passive"))
      (node (ref "U8") (pin "F3") (pinfunction "A14_F3") (pintype "passive"))
      (node (ref "X5") (pin "50") (pinfunction "50_50") (pintype "passive"))
      (node (ref "X6") (pin "50") (pinfunction "50_50") (pintype "passive"))
      (node (ref "X7") (pin "50") (pinfunction "50_50") (pintype "passive"))
    )
    (net (code "19") (name "/A16") (class "Default")
      (node (ref "U5") (pin "88") (pinfunction "PD3/DE1/ADR16_88") (pintype "passive"))
      (node (ref "U7") (pin "F4") (pinfunction "A15_F4") (pintype "passive"))
      (node (ref "U8") (pin "F4") (pinfunction "A15_F4") (pintype "passive"))
      (node (ref "X5") (pin "52") (pinfunction "52_52") (pintype "passive"))
      (node (ref "X6") (pin "52") (pinfunction "52_52") (pintype "passive"))
      (node (ref "X7") (pin "52") (pinfunction "52_52") (pintype "passive"))
    )
    (net (code "20") (name "/A17") (class "Default")
      (node (ref "U5") (pin "73") (pinfunction "PD6/CTS1/ADR17_73") (pintype "passive"))
      (node (ref "U7") (pin "E4") (pinfunction "A16_E4") (pintype "passive"))
      (node (ref "U8") (pin "E4") (pinfunction "A16_E4") (pintype "passive"))
      (node (ref "X5") (pin "54") (pinfunction "54_54") (pintype "passive"))
      (node (ref "X6") (pin "54") (pinfunction "54_54") (pintype "passive"))
      (node (ref "X7") (pin "54") (pinfunction "54_54") (pintype "passive"))
    )
    (net (code "21") (name "/A18") (class "Default")
      (node (ref "U5") (pin "87") (pinfunction "PD4/RXD1/ADR18_87") (pintype "passive"))
      (node (ref "U7") (pin "D3") (pinfunction "A17_D3") (pintype "passive"))
      (node (ref "U8") (pin "D3") (pinfunction "A17_D3") (pintype "passive"))
      (node (ref "X5") (pin "56") (pinfunction "56_56") (pintype "passive"))
      (node (ref "X6") (pin "56") (pinfunction "56_56") (pintype "passive"))
      (node (ref "X7") (pin "56") (pinfunction "56_56") (pintype "passive"))
    )
    (net (code "22") (name "/A19") (class "Default")
      (node (ref "U5") (pin "86") (pinfunction "PD5/TXD1/ADR19_86") (pintype "passive"))
      (node (ref "U7") (pin "H1") (pinfunction "A18_H1") (pintype "passive"))
      (node (ref "U8") (pin "H1") (pinfunction "A18_H1") (pintype "passive"))
      (node (ref "X5") (pin "58") (pinfunction "58_58") (pintype "passive"))
      (node (ref "X6") (pin "58") (pinfunction "58_58") (pintype "passive"))
      (node (ref "X7") (pin "58") (pinfunction "58_58") (pintype "passive"))
    )
    (net (code "23") (name "/A20") (class "Default")
      (node (ref "U5") (pin "22") (pinfunction "PD0/PWMH1/ADR20_22") (pintype "passive"))
      (node (ref "U7") (pin "G2") (pinfunction "A19_G2") (pintype "passive"))
      (node (ref "U8") (pin "G2") (pinfunction "A19_G2") (pintype "passive"))
      (node (ref "X5") (pin "60") (pinfunction "60_60") (pintype "passive"))
      (node (ref "X6") (pin "60") (pinfunction "60_60") (pintype "passive"))
      (node (ref "X7") (pin "60") (pinfunction "60_60") (pintype "passive"))
    )
    (net (code "24") (name "/A21") (class "Default")
      (node (ref "U5") (pin "21") (pinfunction "PD1/PWML1/ADR21_21") (pintype "passive"))
      (node (ref "U7") (pin "H6") (pinfunction "A20_H6") (pintype "passive"))
      (node (ref "U8") (pin "H6") (pinfunction "A20_H6") (pintype "passive"))
      (node (ref "X5") (pin "62") (pinfunction "62_62") (pintype "passive"))
      (node (ref "X6") (pin "62") (pinfunction "62_62") (pintype "passive"))
      (node (ref "X7") (pin "62") (pinfunction "62_62") (pintype "passive"))
    )
    (net (code "25") (name "/A22") (class "Default")
      (node (ref "U5") (pin "2") (pinfunction "PD2/PWMH2/ADR22_2") (pintype "passive"))
      (node (ref "U7") (pin "E3") (pinfunction "A21_E3") (pintype "passive"))
      (node (ref "U8") (pin "E3") (pinfunction "A21_E3") (pintype "passive"))
      (node (ref "X5") (pin "64") (pinfunction "64_64") (pintype "passive"))
      (node (ref "X6") (pin "64") (pinfunction "64_64") (pintype "passive"))
      (node (ref "X7") (pin "64") (pinfunction "64_64") (pintype "passive"))
    )
    (net (code "26") (name "/A23") (class "Default")
      (node (ref "U5") (pin "71") (pinfunction "PD7/PWML2/ADR23_71") (pintype "passive"))
      (node (ref "X5") (pin "66") (pinfunction "66_66") (pintype "passive"))
      (node (ref "X6") (pin "66") (pinfunction "66_66") (pintype "passive"))
      (node (ref "X7") (pin "66") (pinfunction "66_66") (pintype "passive"))
    )
    (net (code "27") (name "/BLUE") (class "Default")
      (node (ref "D2") (pin "6") (pintype "passive"))
      (node (ref "J2") (pin "3") (pinfunction "3_3") (pintype "passive"))
      (node (ref "R20") (pin "2") (pintype "passive"))
      (node (ref "R21") (pin "2") (pintype "passive"))
      (node (ref "R24") (pin "2") (pintype "passive"))
      (node (ref "R25") (pin "2") (pintype "passive"))
      (node (ref "R26") (pin "2") (pintype "passive"))
      (node (ref "R29") (pin "2") (pintype "passive"))
      (node (ref "R31") (pin "2") (pintype "passive"))
    )
    (net (code "28") (name "/CLK") (class "Default")
      (node (ref "U1") (pin "8") (pintype "output"))
      (node (ref "X5") (pin "68") (pinfunction "68_68") (pintype "passive"))
      (node (ref "X6") (pin "68") (pinfunction "68_68") (pintype "passive"))
      (node (ref "X7") (pin "68") (pinfunction "68_68") (pintype "passive"))
    )
    (net (code "29") (name "/CTS") (class "Default")
      (node (ref "J3") (pin "8") (pinfunction "8_8") (pintype "passive"))
      (node (ref "R34") (pin "2") (pintype "passive"))
    )
    (net (code "30") (name "/D0") (class "Default")
      (node (ref "U5") (pin "15") (pinfunction "PE0/DATA0_15") (pintype "passive"))
      (node (ref "U7") (pin "B1") (pinfunction "IO8_B1") (pintype "passive"))
      (node (ref "U7") (pin "B6") (pinfunction "IO0_B6") (pintype "passive"))
      (node (ref "U8") (pin "B1") (pinfunction "IO8_B1") (pintype "passive"))
      (node (ref "U8") (pin "B6") (pinfunction "IO0_B6") (pintype "passive"))
      (node (ref "X5") (pin "5") (pinfunction "5_5") (pintype "passive"))
      (node (ref "X6") (pin "5") (pinfunction "5_5") (pintype "passive"))
      (node (ref "X7") (pin "5") (pinfunction "5_5") (pintype "passive"))
    )
    (net (code "31") (name "/D1") (class "Default")
      (node (ref "U5") (pin "14") (pinfunction "PE1/DATA1_14") (pintype "passive"))
      (node (ref "U7") (pin "C1") (pinfunction "IO9_C1") (pintype "passive"))
      (node (ref "U7") (pin "C5") (pinfunction "IO1_C5") (pintype "passive"))
      (node (ref "U8") (pin "C1") (pinfunction "IO9_C1") (pintype "passive"))
      (node (ref "U8") (pin "C5") (pinfunction "IO1_C5") (pintype "passive"))
      (node (ref "X5") (pin "7") (pinfunction "7_7") (pintype "passive"))
      (node (ref "X6") (pin "7") (pinfunction "7_7") (pintype "passive"))
      (node (ref "X7") (pin "7") (pinfunction "7_7") (pintype "passive"))
    )
    (net (code "32") (name "/D2") (class "Default")
      (node (ref "U5") (pin "13") (pinfunction "PE2/DATA2_13") (pintype "passive"))
      (node (ref "U7") (pin "C2") (pinfunction "IO10_C2") (pintype "passive"))
      (node (ref "U7") (pin "C6") (pinfunction "IO2_C6") (pintype "passive"))
      (node (ref "U8") (pin "C2") (pinfunction "IO10_C2") (pintype "passive"))
      (node (ref "U8") (pin "C6") (pinfunction "IO2_C6") (pintype "passive"))
      (node (ref "X5") (pin "9") (pinfunction "9_9") (pintype "passive"))
      (node (ref "X6") (pin "9") (pinfunction "9_9") (pintype "passive"))
      (node (ref "X7") (pin "9") (pinfunction "9_9") (pintype "passive"))
    )
    (net (code "33") (name "/D3") (class "Default")
      (node (ref "U5") (pin "11") (pinfunction "PE3/DATA3_11") (pintype "passive"))
      (node (ref "U7") (pin "D2") (pinfunction "IO11_D2") (pintype "passive"))
      (node (ref "U7") (pin "D5") (pinfunction "IO3_D5") (pintype "passive"))
      (node (ref "U8") (pin "D2") (pinfunction "IO11_D2") (pintype "passive"))
      (node (ref "U8") (pin "D5") (pinfunction "IO3_D5") (pintype "passive"))
      (node (ref "X5") (pin "11") (pinfunction "11_11") (pintype "passive"))
      (node (ref "X6") (pin "11") (pinfunction "11_11") (pintype "passive"))
      (node (ref "X7") (pin "11") (pinfunction "11_11") (pintype "passive"))
    )
    (net (code "34") (name "/D4") (class "Default")
      (node (ref "U5") (pin "10") (pinfunction "PE4/DATA4_10") (pintype "passive"))
      (node (ref "U7") (pin "E2") (pinfunction "IO12_E2") (pintype "passive"))
      (node (ref "U7") (pin "E5") (pinfunction "IO4_E5") (pintype "passive"))
      (node (ref "U8") (pin "E2") (pinfunction "IO12_E2") (pintype "passive"))
      (node (ref "U8") (pin "E5") (pinfunction "IO4_E5") (pintype "passive"))
      (node (ref "X5") (pin "13") (pinfunction "13_13") (pintype "passive"))
      (node (ref "X6") (pin "13") (pinfunction "13_13") (pintype "passive"))
      (node (ref "X7") (pin "13") (pinfunction "13_13") (pintype "passive"))
    )
    (net (code "35") (name "/D5") (class "Default")
      (node (ref "U5") (pin "66") (pinfunction "PE5/DATA5_66") (pintype "passive"))
      (node (ref "U7") (pin "F2") (pinfunction "IO13_F2") (pintype "passive"))
      (node (ref "U7") (pin "F5") (pinfunction "IO5_F5") (pintype "passive"))
      (node (ref "U8") (pin "F2") (pinfunction "IO13_F2") (pintype "passive"))
      (node (ref "U8") (pin "F5") (pinfunction "IO5_F5") (pintype "passive"))
      (node (ref "X5") (pin "15") (pinfunction "15_15") (pintype "passive"))
      (node (ref "X6") (pin "15") (pinfunction "15_15") (pintype "passive"))
      (node (ref "X7") (pin "15") (pinfunction "15_15") (pintype "passive"))
    )
    (net (code "36") (name "/D6") (class "Default")
      (node (ref "U5") (pin "65") (pinfunction "PE6/DATA6_65") (pintype "passive"))
      (node (ref "U7") (pin "F1") (pinfunction "IO14_F1") (pintype "passive"))
      (node (ref "U7") (pin "F6") (pinfunction "IO6_F6") (pintype "passive"))
      (node (ref "U8") (pin "F1") (pinfunction "IO14_F1") (pintype "passive"))
      (node (ref "U8") (pin "F6") (pinfunction "IO6_F6") (pintype "passive"))
      (node (ref "X5") (pin "17") (pinfunction "17_17") (pintype "passive"))
      (node (ref "X6") (pin "17") (pinfunction "17_17") (pintype "passive"))
      (node (ref "X7") (pin "17") (pinfunction "17_17") (pintype "passive"))
    )
    (net (code "37") (name "/D7") (class "Default")
      (node (ref "U5") (pin "64") (pinfunction "PE7/DATA7_64") (pintype "passive"))
      (node (ref "U7") (pin "G1") (pinfunction "IO15_G1") (pintype "passive"))
      (node (ref "U7") (pin "G6") (pinfunction "IO7_G6") (pintype "passive"))
      (node (ref "U8") (pin "G1") (pinfunction "IO15_G1") (pintype "passive"))
      (node (ref "U8") (pin "G6") (pinfunction "IO7_G6") (pintype "passive"))
      (node (ref "X5") (pin "19") (pinfunction "19_19") (pintype "passive"))
      (node (ref "X6") (pin "19") (pinfunction "19_19") (pintype "passive"))
      (node (ref "X7") (pin "19") (pinfunction "19_19") (pintype "passive"))
    )
    (net (code "38") (name "/DBG") (class "Default")
      (node (ref "R39") (pin "2") (pintype "passive"))
      (node (ref "U5") (pin "54") (pinfunction "DBG_54") (pintype "passive"))
      (node (ref "X9") (pin "4") (pinfunction "4_4") (pintype "passive"))
    )
    (net (code "42") (name "/GP0") (class "Default")
      (node (ref "U5") (pin "34") (pinfunction "PB0/ANA0/T0IN0_34") (pintype "passive"))
      (node (ref "X5") (pin "6") (pinfunction "6_6") (pintype "passive"))
      (node (ref "X6") (pin "6") (pinfunction "6_6") (pintype "passive"))
      (node (ref "X7") (pin "6") (pinfunction "6_6") (pintype "passive"))
    )
    (net (code "43") (name "/GP1") (class "Default")
      (node (ref "U5") (pin "35") (pinfunction "PB1/ANA1/T0IN1_35") (pintype "passive"))
      (node (ref "X5") (pin "8") (pinfunction "8_8") (pintype "passive"))
      (node (ref "X6") (pin "8") (pinfunction "8_8") (pintype "passive"))
      (node (ref "X7") (pin "8") (pinfunction "8_8") (pintype "passive"))
    )
    (net (code "44") (name "/GP2") (class "Default")
      (node (ref "U5") (pin "41") (pinfunction "PB2/ANA2/T0IN2_41") (pintype "passive"))
      (node (ref "X5") (pin "10") (pinfunction "10_10") (pintype "passive"))
      (node (ref "X6") (pin "10") (pinfunction "10_10") (pintype "passive"))
      (node (ref "X7") (pin "10") (pinfunction "10_10") (pintype "passive"))
    )
    (net (code "45") (name "/GP3") (class "Default")
      (node (ref "U5") (pin "40") (pinfunction "PB3/ANA3/OPOUT_40") (pintype "passive"))
      (node (ref "X5") (pin "12") (pinfunction "12_12") (pintype "passive"))
      (node (ref "X6") (pin "12") (pinfunction "12_12") (pintype "passive"))
      (node (ref "X7") (pin "12") (pinfunction "12_12") (pintype "passive"))
    )
    (net (code "46") (name "/GP4") (class "Default")
      (node (ref "U5") (pin "36") (pinfunction "PB4/ANA4_36") (pintype "passive"))
      (node (ref "X5") (pin "14") (pinfunction "14_14") (pintype "passive"))
      (node (ref "X6") (pin "14") (pinfunction "14_14") (pintype "passive"))
      (node (ref "X7") (pin "14") (pinfunction "14_14") (pintype "passive"))
    )
    (net (code "47") (name "/GP5") (class "Default")
      (node (ref "U5") (pin "37") (pinfunction "PB5/ANA5_37") (pintype "passive"))
      (node (ref "X5") (pin "16") (pinfunction "16_16") (pintype "passive"))
      (node (ref "X6") (pin "16") (pinfunction "16_16") (pintype "passive"))
      (node (ref "X7") (pin "16") (pinfunction "16_16") (pintype "passive"))
    )
    (net (code "48") (name "/GP6") (class "Default")
      (node (ref "U5") (pin "38") (pinfunction "PB6/ANA6/OPINP/CINN_38") (pintype "passive"))
      (node (ref "X5") (pin "18") (pinfunction "18_18") (pintype "passive"))
      (node (ref "X6") (pin "18") (pinfunction "18_18") (pintype "passive"))
      (node (ref "X7") (pin "18") (pinfunction "18_18") (pintype "passive"))
    )
    (net (code "49") (name "/GP7") (class "Default")
      (node (ref "U5") (pin "39") (pinfunction "PB7/ANA7/OPINN_39") (pintype "passive"))
      (node (ref "X5") (pin "20") (pinfunction "20_20") (pintype "passive"))
      (node (ref "X6") (pin "20") (pinfunction "20_20") (pintype "passive"))
      (node (ref "X7") (pin "20") (pinfunction "20_20") (pintype "passive"))
    )
    (net (code "50") (name "/GP8") (class "Default")
      (node (ref "J1") (pin "6") (pintype "passive"))
      (node (ref "U5") (pin "1") (pinfunction "PA0/T0IN/T0OUT/DMA0REQ_1") (pintype "passive"))
      (node (ref "X5") (pin "22") (pinfunction "22_22") (pintype "passive"))
      (node (ref "X6") (pin "22") (pinfunction "22_22") (pintype "passive"))
      (node (ref "X7") (pin "22") (pinfunction "22_22") (pintype "passive"))
    )
    (net (code "51") (name "/GP9") (class "Default")
      (node (ref "J1") (pin "2") (pintype "passive"))
      (node (ref "U5") (pin "95") (pinfunction "PA1/T0OUT/DMA0ACK_95") (pintype "passive"))
      (node (ref "X5") (pin "24") (pinfunction "24_24") (pintype "passive"))
      (node (ref "X6") (pin "24") (pinfunction "24_24") (pintype "passive"))
      (node (ref "X7") (pin "24") (pinfunction "24_24") (pintype "passive"))
    )
    (net (code "52") (name "/GP10") (class "Default")
      (node (ref "J1") (pin "5") (pintype "passive"))
      (node (ref "U5") (pin "52") (pinfunction "PC0/T1IN/T1OUT/DMA1REQ/CINN_52") (pintype "passive"))
      (node (ref "X5") (pin "26") (pinfunction "26_26") (pintype "passive"))
      (node (ref "X6") (pin "26") (pinfunction "26_26") (pintype "passive"))
      (node (ref "X7") (pin "26") (pinfunction "26_26") (pintype "passive"))
    )
    (net (code "53") (name "/GP11") (class "Default")
      (node (ref "J1") (pin "1") (pintype "passive"))
      (node (ref "U5") (pin "53") (pinfunction "PC1/T1OUT/DMA1ACK/COMPOUT_53") (pintype "passive"))
      (node (ref "X5") (pin "28") (pinfunction "28_28") (pintype "passive"))
      (node (ref "X6") (pin "28") (pinfunction "28_28") (pintype "passive"))
      (node (ref "X7") (pin "28") (pinfunction "28_28") (pintype "passive"))
    )
    (net (code "54") (name "/GREEN") (class "Default")
      (node (ref "D2") (pin "5") (pintype "passive"))
      (node (ref "J2") (pin "2") (pinfunction "2_2") (pintype "passive"))
      (node (ref "R13") (pin "2") (pintype "passive"))
      (node (ref "R14") (pin "2") (pintype "passive"))
      (node (ref "R16") (pin "2") (pintype "passive"))
      (node (ref "R17") (pin "2") (pintype "passive"))
      (node (ref "R18") (pin "2") (pintype "passive"))
      (node (ref "R19") (pin "2") (pintype "passive"))
      (node (ref "R22") (pin "2") (pintype "passive"))
    )
    (net (code "55") (name "/HSYNC") (class "Default")
      (node (ref "J2") (pin "13") (pinfunction "13_13") (pintype "passive"))
      (node (ref "R37") (pin "2") (pintype "passive"))
    )
    (net (code "56") (name "/MISO") (class "Default")
      (node (ref "U2") (pin "4") (pinfunction "MISO/I2C_SDA_4") (pintype "passive"))
      (node (ref "U5") (pin "89") (pinfunction "PC5/MISO/CS5_89") (pintype "passive"))
      (node (ref "X10") (pin "7") (pinfunction "DAT0/MISO_7") (pintype "passive"))
      (node (ref "X11") (pin "7") (pinfunction "DAT0/MISO_7") (pintype "passive"))
      (node (ref "X12") (pin "7") (pinfunction "DAT0/MISO_7") (pintype "passive"))
      (node (ref "X5") (pin "42") (pinfunction "42_42") (pintype "passive"))
      (node (ref "X6") (pin "42") (pinfunction "42_42") (pintype "passive"))
      (node (ref "X7") (pin "42") (pinfunction "42_42") (pintype "passive"))
    )
    (net (code "57") (name "/MOSI") (class "Default")
      (node (ref "U2") (pin "5") (pinfunction "MOSI/I2C_SA0_5") (pintype "passive"))
      (node (ref "U5") (pin "85") (pinfunction "PC4/MOSI/DMA2ACK_85") (pintype "passive"))
      (node (ref "X10") (pin "2") (pinfunction "CMD/MOSI_2") (pintype "passive"))
      (node (ref "X11") (pin "2") (pinfunction "CMD/MOSI_2") (pintype "passive"))
      (node (ref "X12") (pin "3") (pinfunction "CMD/MOSI_3") (pintype "passive"))
      (node (ref "X5") (pin "40") (pinfunction "40_40") (pintype "passive"))
      (node (ref "X6") (pin "40") (pinfunction "40_40") (pintype "passive"))
      (node (ref "X7") (pin "40") (pinfunction "40_40") (pintype "passive"))
    )
    (net (code "58") (name "/RD") (class "Default")
      (node (ref "J3") (pin "2") (pinfunction "2_2") (pintype "passive"))
      (node (ref "R33") (pin "2") (pintype "passive"))
    )
    (net (code "59") (name "/RED") (class "Default")
      (node (ref "D2") (pin "4") (pintype "passive"))
      (node (ref "J2") (pin "1") (pinfunction "1_1") (pintype "passive"))
      (node (ref "R10") (pin "2") (pintype "passive"))
      (node (ref "R11") (pin "2") (pintype "passive"))
      (node (ref "R23") (pin "2") (pintype "passive"))
      (node (ref "R5") (pin "2") (pintype "passive"))
      (node (ref "R6") (pin "2") (pintype "passive"))
      (node (ref "R8") (pin "2") (pintype "passive"))
      (node (ref "R9") (pin "2") (pintype "passive"))
    )
    (net (code "61") (name "/RTS") (class "Default")
      (node (ref "J3") (pin "7") (pinfunction "7_7") (pintype "passive"))
      (node (ref "R30") (pin "2") (pintype "passive"))
    )
    (net (code "62") (name "/RXD") (class "Default")
      (node (ref "U3") (pin "12") (pinfunction "R1OUT_12") (pintype "passive"))
      (node (ref "U5") (pin "77") (pinfunction "PA4/RXD0/CS1_77") (pintype "passive"))
    )
    (net (code "63") (name "/SCK") (class "Default")
      (node (ref "U2") (pin "3") (pinfunction "SPI_SCLK/I2C_SCL_3") (pintype "passive"))
      (node (ref "U5") (pin "72") (pinfunction "PC3/SCK/DMA2REQ_72") (pintype "passive"))
      (node (ref "X10") (pin "5") (pinfunction "CLK_5") (pintype "passive"))
      (node (ref "X11") (pin "5") (pinfunction "CLK_5") (pintype "passive"))
      (node (ref "X12") (pin "5") (pinfunction "CLK_5") (pintype "passive"))
      (node (ref "X5") (pin "38") (pinfunction "38_38") (pintype "passive"))
      (node (ref "X6") (pin "38") (pinfunction "38_38") (pintype "passive"))
      (node (ref "X7") (pin "38") (pinfunction "38_38") (pintype "passive"))
    )
    (net (code "64") (name "/SCL") (class "Default")
      (node (ref "R46") (pin "1") (pintype "passive"))
      (node (ref "U5") (pin "75") (pinfunction "PA6/SCL/CS3_75") (pintype "passive"))
      (node (ref "U9") (pin "6") (pinfunction "SCL_6") (pintype "input"))
      (node (ref "X5") (pin "39") (pinfunction "39_39") (pintype "passive"))
      (node (ref "X6") (pin "39") (pinfunction "39_39") (pintype "passive"))
      (node (ref "X7") (pin "39") (pinfunction "39_39") (pintype "passive"))
    )
    (net (code "65") (name "/SDA") (class "Default")
      (node (ref "R45") (pin "1") (pintype "passive"))
      (node (ref "U5") (pin "74") (pinfunction "PA7/SDA/CS4_74") (pintype "passive"))
      (node (ref "U9") (pin "5") (pinfunction "SDA_5") (pintype "bidirectional"))
      (node (ref "X5") (pin "41") (pinfunction "41_41") (pintype "passive"))
      (node (ref "X6") (pin "41") (pinfunction "41_41") (pintype "passive"))
      (node (ref "X7") (pin "41") (pinfunction "41_41") (pintype "passive"))
    )
    (net (code "66") (name "/TD") (class "Default")
      (node (ref "J3") (pin "3") (pinfunction "3_3") (pintype "passive"))
      (node (ref "R28") (pin "2") (pintype "passive"))
    )
    (net (code "67") (name "/TXD") (class "Default")
      (node (ref "U3") (pin "11") (pinfunction "T1IN_11") (pintype "passive"))
      (node (ref "U5") (pin "76") (pinfunction "PA5/TXD0/CS2_76") (pintype "passive"))
    )
    (net (code "68") (name "/VSYNC") (class "Default")
      (node (ref "J2") (pin "14") (pinfunction "14_14") (pintype "passive"))
      (node (ref "R38") (pin "2") (pintype "passive"))
    )
    (net (code "69") (name "/WP1") (class "Default")
      (node (ref "R61") (pin "1") (pintype "passive"))
      (node (ref "U5") (pin "81") (pinfunction "PJ6/DATA14_81") (pintype "passive"))
      (node (ref "X10") (pin "WP") (pinfunction "WP_WP") (pintype "passive"))
    )
    (net (code "70") (name "/WP2") (class "Default")
      (node (ref "R57") (pin "1") (pintype "passive"))
      (node (ref "U5") (pin "98") (pinfunction "PJ2/DATA10_98") (pintype "passive"))
      (node (ref "X11") (pin "WP") (pinfunction "WP_WP") (pintype "passive"))
    )
    (net (code "71") (name "/~0000") (class "Default")
      (node (ref "R65") (pin "1") (pintype "passive"))
      (node (ref "U5") (pin "27") (pinfunction "PK2/CS0_27") (pintype "passive"))
      (node (ref "U7") (pin "B5") (pinfunction "~CE_B5") (pintype "passive"))
      (node (ref "X5") (pin "30") (pinfunction "30_30") (pintype "passive"))
      (node (ref "X6") (pin "30") (pinfunction "30_30") (pintype "passive"))
      (node (ref "X7") (pin "30") (pinfunction "30_30") (pintype "passive"))
    )
    (net (code "72") (name "/~8000") (class "Default")
      (node (ref "R66") (pin "1") (pintype "passive"))
      (node (ref "U5") (pin "26") (pinfunction "PK3/CS1_26") (pintype "passive"))
      (node (ref "U8") (pin "B5") (pinfunction "~CE_B5") (pintype "passive"))
      (node (ref "X5") (pin "32") (pinfunction "32_32") (pintype "passive"))
      (node (ref "X6") (pin "32") (pinfunction "32_32") (pintype "passive"))
      (node (ref "X7") (pin "32") (pinfunction "32_32") (pintype "passive"))
    )
    (net (code "73") (name "/~BHE") (class "Default")
      (node (ref "R63") (pin "1") (pintype "passive"))
      (node (ref "U10") (pin "6") (pinfunction "I2_6") (pintype "input"))
      (node (ref "U5") (pin "29") (pinfunction "PK0/BHEN_29") (pintype "passive"))
      (node (ref "U7") (pin "B2") (pinfunction "~UB_B2") (pintype "passive"))
      (node (ref "U8") (pin "B2") (pinfunction "~UB_B2") (pintype "passive"))
      (node (ref "X5") (pin "27") (pinfunction "27_27") (pintype "passive"))
      (node (ref "X6") (pin "27") (pinfunction "27_27") (pintype "passive"))
      (node (ref "X7") (pin "27") (pinfunction "27_27") (pintype "passive"))
    )
    (net (code "74") (name "/~BLE") (class "Default")
      (node (ref "R64") (pin "1") (pintype "passive"))
      (node (ref "U10") (pin "4") (pinfunction "Y_4") (pintype "output"))
      (node (ref "U7") (pin "A1") (pinfunction "~LB_A1") (pintype "passive"))
      (node (ref "U8") (pin "A1") (pinfunction "~LB_A1") (pintype "passive"))
      (node (ref "X5") (pin "25") (pinfunction "25_25") (pintype "passive"))
      (node (ref "X6") (pin "25") (pinfunction "25_25") (pintype "passive"))
      (node (ref "X7") (pin "25") (pinfunction "25_25") (pintype "passive"))
    )
    (net (code "75") (name "/~BLZ") (class "Default")
      (node (ref "U10") (pin "1") (pinfunction "I1_1") (pintype "input"))
      (node (ref "U5") (pin "28") (pinfunction "PK1/BLEN_28") (pintype "passive"))
    )
    (net (code "76") (name "/~CTS") (class "Default")
      (node (ref "R35") (pin "2") (pintype "passive"))
      (node (ref "U3") (pin "9") (pinfunction "R2OUT_9") (pintype "passive"))
      (node (ref "U5") (pin "55") (pinfunction "PC6/T2IN/T2OUT/PWMH0_55") (pintype "passive"))
    )
    (net (code "77") (name "/~DT1") (class "Default")
      (node (ref "R60") (pin "1") (pintype "passive"))
      (node (ref "U5") (pin "82") (pinfunction "PJ5/DATA13_82") (pintype "passive"))
      (node (ref "X10") (pin "DET") (pinfunction "DET_DET") (pintype "passive"))
    )
    (net (code "78") (name "/~DT2") (class "Default")
      (node (ref "R56") (pin "1") (pintype "passive"))
      (node (ref "U5") (pin "99") (pinfunction "PJ1/DATA9_99") (pintype "passive"))
      (node (ref "X11") (pin "DET") (pinfunction "DET_DET") (pintype "passive"))
    )
    (net (code "79") (name "/~EPFI") (class "Default")
      (node (ref "R7") (pin "1") (pintype "passive"))
      (node (ref "U1") (pin "6") (pintype "output"))
      (node (ref "X5") (pin "34") (pinfunction "34_34") (pintype "passive"))
      (node (ref "X6") (pin "34") (pinfunction "34_34") (pintype "passive"))
      (node (ref "X7") (pin "34") (pinfunction "34_34") (pintype "passive"))
    )
    (net (code "80") (name "/~EVE") (class "Default")
      (node (ref "R58") (pin "1") (pintype "passive"))
      (node (ref "U2") (pin "6") (pinfunction "CS_N/I2C_SA1_6") (pintype "passive"))
      (node (ref "U5") (pin "97") (pinfunction "PJ3/DATA11_97") (pintype "passive"))
    )
    (net (code "81") (name "/~EXP") (class "Default")
      (node (ref "R50") (pin "1") (pintype "passive"))
      (node (ref "U5") (pin "3") (pinfunction "PC2/SS/CS4_3") (pintype "passive"))
      (node (ref "X5") (pin "36") (pinfunction "36_36") (pintype "passive"))
      (node (ref "X6") (pin "36") (pinfunction "36_36") (pintype "passive"))
      (node (ref "X7") (pin "36") (pinfunction "36_36") (pintype "passive"))
    )
    (net (code "82") (name "/~F000") (class "Default")
      (node (ref "R67") (pin "1") (pintype "passive"))
      (node (ref "U5") (pin "46") (pinfunction "PK4/CS2_46") (pintype "passive"))
      (node (ref "X5") (pin "29") (pinfunction "29_29") (pintype "passive"))
      (node (ref "X6") (pin "29") (pinfunction "29_29") (pintype "passive"))
      (node (ref "X7") (pin "29") (pinfunction "29_29") (pintype "passive"))
    )
    (net (code "83") (name "/~FFC8") (class "Default")
      (node (ref "R68") (pin "1") (pintype "passive"))
      (node (ref "U5") (pin "47") (pinfunction "PK5/CS3_47") (pintype "passive"))
      (node (ref "X5") (pin "31") (pinfunction "31_31") (pintype "passive"))
      (node (ref "X6") (pin "31") (pinfunction "31_31") (pintype "passive"))
      (node (ref "X7") (pin "31") (pinfunction "31_31") (pintype "passive"))
    )
    (net (code "84") (name "/~FFD0") (class "Default")
      (node (ref "R69") (pin "1") (pintype "passive"))
      (node (ref "U5") (pin "48") (pinfunction "PK6/CS4_48") (pintype "passive"))
      (node (ref "X5") (pin "33") (pinfunction "33_33") (pintype "passive"))
      (node (ref "X6") (pin "33") (pinfunction "33_33") (pintype "passive"))
      (node (ref "X7") (pin "33") (pinfunction "33_33") (pintype "passive"))
    )
    (net (code "85") (name "/~FFD8") (class "Default")
      (node (ref "R70") (pin "1") (pintype "passive"))
      (node (ref "U5") (pin "49") (pinfunction "PK7/CS5_49") (pintype "passive"))
      (node (ref "X5") (pin "35") (pinfunction "35_35") (pintype "passive"))
      (node (ref "X6") (pin "35") (pinfunction "35_35") (pintype "passive"))
      (node (ref "X7") (pin "35") (pinfunction "35_35") (pintype "passive"))
    )
    (net (code "86") (name "/~INTI") (class "Default")
      (node (ref "R15") (pin "1") (pintype "passive"))
      (node (ref "R3") (pin "2") (pintype "passive"))
      (node (ref "R48") (pin "1") (pintype "passive"))
      (node (ref "U2") (pin "11") (pinfunction "INT_N_11") (pintype "passive"))
      (node (ref "U5") (pin "94") (pinfunction "PA2/DE0/FAULTY_94") (pintype "passive"))
    )
    (net (code "87") (name "/~INTX") (class "Default")
      (node (ref "R47") (pin "1") (pintype "passive"))
      (node (ref "U5") (pin "93") (pinfunction "PA3/CTS0/FAULT0_93") (pintype "passive"))
      (node (ref "X5") (pin "37") (pinfunction "37_37") (pintype "passive"))
      (node (ref "X6") (pin "37") (pinfunction "37_37") (pintype "passive"))
      (node (ref "X7") (pin "37") (pinfunction "37_37") (pintype "passive"))
    )
    (net (code "88") (name "/~RD") (class "Default")
      (node (ref "R52") (pin "1") (pintype "passive"))
      (node (ref "U5") (pin "33") (pinfunction "PH1/ANA9/RD_33") (pintype "passive"))
      (node (ref "U7") (pin "A2") (pinfunction "~OE_A2") (pintype "passive"))
      (node (ref "U8") (pin "A2") (pinfunction "~OE_A2") (pintype "passive"))
      (node (ref "X5") (pin "23") (pinfunction "23_23") (pintype "passive"))
      (node (ref "X6") (pin "23") (pinfunction "23_23") (pintype "passive"))
      (node (ref "X7") (pin "23") (pinfunction "23_23") (pintype "passive"))
    )
    (net (code "89") (name "/~RESET") (class "Default")
      (node (ref "R49") (pin "1") (pintype "passive"))
      (node (ref "U5") (pin "5") (pinfunction "RESET_5") (pintype "passive"))
      (node (ref "U6") (pin "1") (pinfunction "~RST_1") (pintype "open_collector"))
      (node (ref "X5") (pin "67") (pinfunction "67_67") (pintype "passive"))
      (node (ref "X6") (pin "67") (pinfunction "67_67") (pintype "passive"))
      (node (ref "X7") (pin "67") (pinfunction "67_67") (pintype "passive"))
      (node (ref "X9") (pin "2") (pinfunction "2_2") (pintype "passive"))
    )
    (net (code "90") (name "/~RF") (class "Default")
      (node (ref "R53") (pin "1") (pintype "passive"))
      (node (ref "U5") (pin "42") (pinfunction "PH2/ANA10/CS0_42") (pintype "passive"))
    )
    (net (code "91") (name "/~RTS") (class "Default")
      (node (ref "D1") (pin "2") (pintype "passive"))
      (node (ref "R36") (pin "2") (pintype "passive"))
      (node (ref "U3") (pin "10") (pinfunction "T2IN_10") (pintype "passive"))
      (node (ref "U5") (pin "56") (pinfunction "PC7/T2OUT/PWML0_56") (pintype "passive"))
    )
    (net (code "92") (name "/~SD0") (class "Default")
      (node (ref "R62") (pin "1") (pintype "passive"))
      (node (ref "U5") (pin "80") (pinfunction "PJ7/DATA15_80") (pintype "passive"))
      (node (ref "X12") (pin "2") (pinfunction "DAT3/~SS_2") (pintype "passive"))
    )
    (net (code "93") (name "/~SD1") (class "Default")
      (node (ref "R59") (pin "1") (pintype "passive"))
      (node (ref "U5") (pin "83") (pinfunction "PJ4/DATA12_83") (pintype "passive"))
      (node (ref "X10") (pin "1") (pinfunction "DAT3/~SS_1") (pintype "passive"))
    )
    (net (code "94") (name "/~SD2") (class "Default")
      (node (ref "R55") (pin "1") (pintype "passive"))
      (node (ref "U5") (pin "100") (pinfunction "PJ0/DATA8_100") (pintype "passive"))
      (node (ref "X11") (pin "1") (pinfunction "DAT3/~SS_1") (pintype "passive"))
    )
    (net (code "95") (name "/~SXM") (class "Default")
      (node (ref "R54") (pin "1") (pintype "passive"))
      (node (ref "U5") (pin "43") (pinfunction "PH3/ANA11/CINP/WAIT_43") (pintype "passive"))
    )
    (net (code "96") (name "/~WR") (class "Default")
      (node (ref "R51") (pin "1") (pintype "passive"))
      (node (ref "U5") (pin "32") (pinfunction "PH0/ANA8/WR_32") (pintype "passive"))
      (node (ref "X5") (pin "21") (pinfunction "21_21") (pintype "passive"))
      (node (ref "X6") (pin "21") (pinfunction "21_21") (pintype "passive"))
      (node (ref "X7") (pin "21") (pinfunction "21_21") (pintype "passive"))
    )
    (net (code "97") (name "/~WRC") (class "Default")
      (node (ref "U7") (pin "G5") (pinfunction "~WE_G5") (pintype "passive"))
      (node (ref "U8") (pin "G5") (pinfunction "~WE_G5") (pintype "passive"))
    )
    (net (code "98") (name "EARTH") (class "Default")
      (node (ref "MOD1") (pin "1") (pinfunction "FG_1") (pintype "power_in"))
      (node (ref "X1") (pin "2") (pinfunction "2_2") (pintype "passive"))
    )
    (net (code "99") (name "GND") (class "Default")
      (node (ref "C1") (pin "2") (pintype "passive"))
      (node (ref "C10") (pin "2") (pintype "passive"))
      (node (ref "C11") (pin "2") (pintype "passive"))
      (node (ref "C12") (pin "2") (pintype "passive"))
      (node (ref "C13") (pin "2") (pintype "passive"))
      (node (ref "C14") (pin "2") (pintype "passive"))
      (node (ref "C15") (pin "2") (pintype "passive"))
      (node (ref "C17") (pin "1") (pintype "passive"))
      (node (ref "C18") (pin "2") (pintype "passive"))
      (node (ref "C20") (pin "1") (pintype "passive"))
      (node (ref "C21") (pin "1") (pintype "passive"))
      (node (ref "C22") (pin "2") (pintype "passive"))
      (node (ref "C24") (pin "2") (pintype "passive"))
      (node (ref "C25") (pin "1") (pintype "passive"))
      (node (ref "C26") (pin "1") (pintype "passive"))
      (node (ref "C27") (pin "1") (pintype "passive"))
      (node (ref "C28") (pin "1") (pintype "passive"))
      (node (ref "C29") (pin "1") (pintype "passive"))
      (node (ref "C3") (pin "1") (pintype "passive"))
      (node (ref "C30") (pin "1") (pintype "passive"))
      (node (ref "C31") (pin "1") (pintype "passive"))
      (node (ref "C32") (pin "1") (pintype "passive"))
      (node (ref "C33") (pin "1") (pintype "passive"))
      (node (ref "C35") (pin "1") (pintype "passive"))
      (node (ref "C36") (pin "2") (pintype "passive"))
      (node (ref "C37") (pin "1") (pintype "passive"))
      (node (ref "C38") (pin "1") (pintype "passive"))
      (node (ref "C39") (pin "1") (pintype "passive"))
      (node (ref "C40") (pin "1") (pintype "passive"))
      (node (ref "C41") (pin "2") (pintype "passive"))
      (node (ref "C42") (pin "2") (pintype "passive"))
      (node (ref "C43") (pin "2") (pintype "passive"))
      (node (ref "C44") (pin "2") (pintype "passive"))
      (node (ref "C45") (pin "2") (pintype "passive"))
      (node (ref "C46") (pin "2") (pintype "passive"))
      (node (ref "C47") (pin "2") (pintype "passive"))
      (node (ref "C48") (pin "2") (pintype "passive"))
      (node (ref "C49") (pin "2") (pintype "passive"))
      (node (ref "C5") (pin "2") (pintype "passive"))
      (node (ref "C50") (pin "1") (pintype "passive"))
      (node (ref "C51") (pin "2") (pintype "passive"))
      (node (ref "C6") (pin "2") (pintype "passive"))
      (node (ref "C7") (pin "2") (pintype "passive"))
      (node (ref "C8") (pin "2") (pintype "passive"))
      (node (ref "C9") (pin "2") (pintype "passive"))
      (node (ref "D2") (pin "1") (pintype "passive"))
      (node (ref "D2") (pin "2") (pintype "passive"))
      (node (ref "D2") (pin "3") (pintype "passive"))
      (node (ref "J1") (pin "0") (pintype "passive"))
      (node (ref "J1") (pin "3") (pintype "passive"))
      (node (ref "J2") (pin "10") (pinfunction "10_10") (pintype "passive"))
      (node (ref "J2") (pin "5") (pinfunction "5_5") (pintype "passive"))
      (node (ref "J2") (pin "6") (pinfunction "6_6") (pintype "passive"))
      (node (ref "J2") (pin "7") (pinfunction "7_7") (pintype "passive"))
      (node (ref "J2") (pin "8") (pinfunction "8_8") (pintype "passive"))
      (node (ref "J2") (pin "9") (pinfunction "9_9") (pintype "passive"))
      (node (ref "J3") (pin "0") (pintype "passive"))
      (node (ref "J3") (pin "5") (pinfunction "5_5") (pintype "passive"))
      (node (ref "J4") (pin "1") (pintype "passive"))
      (node (ref "LED1") (pin "1") (pintype "passive"))
      (node (ref "LED2") (pin "1") (pintype "passive"))
      (node (ref "MOD1") (pin "5") (pinfunction "GND2_5") (pintype "power_in"))
      (node (ref "MOD1") (pin "8") (pinfunction "GND1_8") (pintype "power_in"))
      (node (ref "MOD2") (pin "2") (pinfunction "Vin-_2") (pintype "power_in"))
      (node (ref "MOD2") (pin "4") (pinfunction "GND2_4") (pintype "passive"))
      (node (ref "MOD2") (pin "6") (pinfunction "GND1_6") (pintype "power_in"))
      (node (ref "Q1") (pin "2") (pinfunction "E_2") (pintype "passive"))
      (node (ref "Q2") (pin "1") (pinfunction "G_1") (pintype "passive"))
      (node (ref "Q3") (pin "2") (pinfunction "E_2") (pintype "passive"))
      (node (ref "R21") (pin "1") (pintype "passive"))
      (node (ref "R22") (pin "1") (pintype "passive"))
      (node (ref "R23") (pin "1") (pintype "passive"))
      (node (ref "R35") (pin "1") (pintype "passive"))
      (node (ref "SW2") (pin "1") (pintype "passive"))
      (node (ref "U1") (pin "7") (pinfunction "GND_7") (pintype "passive"))
      (node (ref "U10") (pin "2") (pinfunction "GND_2") (pintype "power_in"))
      (node (ref "U10") (pin "3") (pinfunction "I0_3") (pintype "input"))
      (node (ref "U2") (pin "10") (pinfunction "MODE_10") (pintype "passive"))
      (node (ref "U2") (pin "15") (pinfunction "GND_15") (pintype "passive"))
      (node (ref "U2") (pin "2") (pinfunction "GND_2") (pintype "passive"))
      (node (ref "U2") (pin "23") (pinfunction "GND_23") (pintype "passive"))
      (node (ref "U2") (pin "36") (pinfunction "GND_36") (pintype "passive"))
      (node (ref "U2") (pin "49") (pinfunction "PAD_49") (pintype "passive"))
      (node (ref "U3") (pin "15") (pinfunction "GND_15") (pintype "passive"))
      (node (ref "U5") (pin "12") (pinfunction "VSS_12") (pintype "passive"))
      (node (ref "U5") (pin "16") (pinfunction "VSS_16") (pintype "passive"))
      (node (ref "U5") (pin "25") (pinfunction "VSS_25") (pintype "passive"))
      (node (ref "U5") (pin "45") (pinfunction "AVSS_45") (pintype "passive"))
      (node (ref "U5") (pin "51") (pinfunction "VSS_51") (pintype "passive"))
      (node (ref "U5") (pin "69") (pinfunction "VSS_69") (pintype "passive"))
      (node (ref "U5") (pin "78") (pinfunction "VSS_78") (pintype "passive"))
      (node (ref "U5") (pin "84") (pinfunction "VSS_84") (pintype "passive"))
      (node (ref "U5") (pin "92") (pinfunction "VSS_92") (pintype "passive"))
      (node (ref "U6") (pin "2") (pinfunction "Vss_2") (pintype "power_in"))
      (node (ref "U7") (pin "D1") (pinfunction "GND_D1") (pintype "passive"))
      (node (ref "U7") (pin "E6") (pinfunction "GND_E6") (pintype "passive"))
      (node (ref "U8") (pin "D1") (pinfunction "GND_D1") (pintype "passive"))
      (node (ref "U8") (pin "E6") (pinfunction "GND_E6") (pintype "passive"))
      (node (ref "U9") (pin "4") (pinfunction "GND_4") (pintype "power_in"))
      (node (ref "UC1") (pin "3") (pintype "passive"))
      (node (ref "X10") (pin "0") (pinfunction "MNT_0") (pintype "passive"))
      (node (ref "X10") (pin "3") (pinfunction "GND_3") (pintype "passive"))
      (node (ref "X10") (pin "6") (pinfunction "GND_6") (pintype "passive"))
      (node (ref "X11") (pin "0") (pinfunction "MNT_0") (pintype "passive"))
      (node (ref "X11") (pin "3") (pinfunction "GND_3") (pintype "passive"))
      (node (ref "X11") (pin "6") (pinfunction "GND_6") (pintype "passive"))
      (node (ref "X12") (pin "0") (pinfunction "MNT_0") (pintype "passive"))
      (node (ref "X12") (pin "6") (pinfunction "GND_6") (pintype "passive"))
      (node (ref "X3") (pin "2") (pintype "passive"))
      (node (ref "X4") (pin "6") (pinfunction "6_6") (pintype "passive"))
      (node (ref "X5") (pin "69") (pinfunction "69_69") (pintype "passive"))
      (node (ref "X5") (pin "70") (pinfunction "70_70") (pintype "passive"))
      (node (ref "X5") (pin "71") (pinfunction "71_71") (pintype "passive"))
      (node (ref "X5") (pin "72") (pinfunction "72_72") (pintype "passive"))
      (node (ref "X6") (pin "69") (pinfunction "69_69") (pintype "passive"))
      (node (ref "X6") (pin "70") (pinfunction "70_70") (pintype "passive"))
      (node (ref "X6") (pin "71") (pinfunction "71_71") (pintype "passive"))
      (node (ref "X6") (pin "72") (pinfunction "72_72") (pintype "passive"))
      (node (ref "X7") (pin "69") (pinfunction "69_69") (pintype "passive"))
      (node (ref "X7") (pin "70") (pinfunction "70_70") (pintype "passive"))
      (node (ref "X7") (pin "71") (pinfunction "71_71") (pintype "passive"))
      (node (ref "X7") (pin "72") (pinfunction "72_72") (pintype "passive"))
      (node (ref "X9") (pin "3") (pinfunction "3_3") (pintype "passive"))
      (node (ref "X9") (pin "5") (pinfunction "5_5") (pintype "passive"))
    )
    (net (code "100") (name "Net-(C2-Pad1)") (class "Default")
      (node (ref "C2") (pin "1") (pintype "passive"))
      (node (ref "F1") (pin "1") (pintype "passive"))
      (node (ref "SW1") (pin "1") (pintype "passive"))
    )
    (net (code "101") (name "Net-(C4-Pad1)") (class "Default")
      (node (ref "C4") (pin "1") (pintype "passive"))
      (node (ref "R2") (pin "1") (pintype "passive"))
      (node (ref "U1") (pin "1") (pintype "input"))
      (node (ref "U1") (pin "4") (pintype "input"))
      (node (ref "UC1") (pin "4") (pintype "passive"))
    )
    (net (code "102") (name "Net-(C34-Pad1)") (class "Default")
      (node (ref "C34") (pin "1") (pintype "passive"))
      (node (ref "C39") (pin "2") (pintype "passive"))
      (node (ref "R43") (pin "2") (pintype "passive"))
    )
    (net (code "103") (name "Net-(C34-Pad2)") (class "Default")
      (node (ref "C34") (pin "2") (pintype "passive"))
      (node (ref "J4") (pin "2") (pintype "passive"))
      (node (ref "J4") (pin "3") (pintype "passive"))
    )
    (net (code "104") (name "Net-(C36-Pad1)") (class "Default")
      (node (ref "C36") (pin "1") (pintype "passive"))
      (node (ref "R44") (pin "2") (pintype "passive"))
      (node (ref "U1") (pin "12") (pintype "input"))
      (node (ref "U1") (pin "13") (pintype "input"))
      (node (ref "Y2") (pin "2") (pintype "passive"))
    )
    (net (code "105") (name "Net-(C37-Pad2)") (class "Default")
      (node (ref "C37") (pin "2") (pintype "passive"))
      (node (ref "R41") (pin "2") (pintype "passive"))
      (node (ref "R42") (pin "1") (pintype "passive"))
    )
    (net (code "106") (name "Net-(C38-Pad2)") (class "Default")
      (node (ref "C38") (pin "2") (pintype "passive"))
      (node (ref "R42") (pin "2") (pintype "passive"))
      (node (ref "R43") (pin "1") (pintype "passive"))
    )
    (net (code "107") (name "Net-(C43-Pad1)") (class "Default")
      (node (ref "C43") (pin "1") (pintype "passive"))
      (node (ref "C44") (pin "1") (pintype "passive"))
      (node (ref "C45") (pin "1") (pintype "passive"))
      (node (ref "C46") (pin "1") (pintype "passive"))
      (node (ref "C51") (pin "1") (pintype "passive"))
      (node (ref "JP1") (pin "2") (pintype "passive"))
      (node (ref "U7") (pin "D6") (pinfunction "VDD_D6") (pintype "passive"))
      (node (ref "U7") (pin "E1") (pinfunction "VDD_E1") (pintype "passive"))
      (node (ref "U8") (pin "D6") (pinfunction "VDD_D6") (pintype "passive"))
      (node (ref "U8") (pin "E1") (pinfunction "VDD_E1") (pintype "passive"))
    )
    (net (code "108") (name "Net-(D1-Pad1)") (class "Default")
      (node (ref "D1") (pin "1") (pintype "passive"))
      (node (ref "R7") (pin "2") (pintype "passive"))
    )
    (net (code "109") (name "Net-(LED1-Pad2)") (class "Default")
      (node (ref "LED1") (pin "2") (pintype "passive"))
      (node (ref "R27") (pin "1") (pintype "passive"))
    )
    (net (code "110") (name "Net-(LED2-Pad2)") (class "Default")
      (node (ref "LED2") (pin "2") (pintype "passive"))
      (node (ref "R32") (pin "1") (pintype "passive"))
    )
    (net (code "111") (name "Net-(LED3-Pad1)") (class "Default")
      (node (ref "LED3") (pin "1") (pintype "passive"))
      (node (ref "R53") (pin "2") (pintype "passive"))
    )
    (net (code "112") (name "Net-(LED4-Pad1)") (class "Default")
      (node (ref "LED4") (pin "1") (pintype "passive"))
      (node (ref "R54") (pin "2") (pintype "passive"))
    )
    (net (code "113") (name "Net-(LED5-Pad1)") (class "Default")
      (node (ref "LED5") (pin "1") (pintype "passive"))
      (node (ref "R55") (pin "2") (pintype "passive"))
    )
    (net (code "114") (name "Net-(LED6-Pad1)") (class "Default")
      (node (ref "LED6") (pin "1") (pintype "passive"))
      (node (ref "R59") (pin "2") (pintype "passive"))
    )
    (net (code "115") (name "Net-(LED7-Pad1)") (class "Default")
      (node (ref "LED7") (pin "1") (pintype "passive"))
      (node (ref "R62") (pin "2") (pintype "passive"))
    )
    (net (code "116") (name "Net-(MOD1-AC(L))") (class "Default")
      (node (ref "F1") (pin "2") (pintype "passive"))
      (node (ref "MOD1") (pin "3") (pinfunction "AC(L)_3") (pintype "power_in"))
      (node (ref "R1") (pin "1") (pintype "passive"))
    )
    (net (code "117") (name "Net-(MOD1-AC(N))") (class "Default")
      (node (ref "C2") (pin "2") (pintype "passive"))
      (node (ref "MOD1") (pin "2") (pinfunction "AC(N)_2") (pintype "power_in"))
      (node (ref "UC1") (pin "2") (pintype "passive"))
      (node (ref "X1") (pin "3") (pinfunction "3_3") (pintype "passive"))
    )
    (net (code "118") (name "Net-(MOD2-Vin+)") (class "Default")
      (node (ref "C14") (pin "1") (pintype "passive"))
      (node (ref "MOD2") (pin "1") (pinfunction "Vin+_1") (pintype "power_in"))
      (node (ref "Q1") (pin "1") (pinfunction "B_1") (pintype "passive"))
      (node (ref "Q2") (pin "2") (pinfunction "S_2") (pintype "passive"))
    )
    (net (code "119") (name "Net-(Q1-C)") (class "Default")
      (node (ref "Q1") (pin "3") (pinfunction "C_3") (pintype "passive"))
      (node (ref "R4") (pin "2") (pintype "passive"))
      (node (ref "U1") (pin "2") (pintype "input"))
      (node (ref "U1") (pin "5") (pintype "input"))
    )
    (net (code "120") (name "Net-(Q2-D)") (class "Default")
      (node (ref "Q2") (pin "3") (pinfunction "D_3") (pintype "passive"))
      (node (ref "SW1") (pin "4") (pintype "passive"))
    )
    (net (code "121") (name "Net-(Q3-B)") (class "Default")
      (node (ref "J4") (pin "4") (pintype "passive"))
      (node (ref "J4") (pin "5") (pintype "passive"))
      (node (ref "Q3") (pin "1") (pinfunction "B_1") (pintype "passive"))
    )
    (net (code "122") (name "Net-(Q3-C)") (class "Default")
      (node (ref "D3") (pin "2") (pintype "passive"))
      (node (ref "Q3") (pin "3") (pinfunction "C_3") (pintype "passive"))
      (node (ref "SPK1") (pin "2") (pinfunction "-_2") (pintype "passive"))
    )
    (net (code "123") (name "Net-(R1-Pad2)") (class "Default")
      (node (ref "R1") (pin "2") (pintype "passive"))
      (node (ref "UC1") (pin "1") (pintype "passive"))
    )
    (net (code "124") (name "Net-(R3-Pad1)") (class "Default")
      (node (ref "R3") (pin "1") (pintype "passive"))
      (node (ref "U1") (pin "3") (pintype "output"))
    )
    (net (code "125") (name "Net-(SPK1-+)") (class "Default")
      (node (ref "D3") (pin "1") (pintype "passive"))
      (node (ref "R40") (pin "1") (pintype "passive"))
      (node (ref "SPK1") (pin "1") (pinfunction "+_1") (pintype "passive"))
    )
    (net (code "126") (name "Net-(SW1-Pad2)") (class "Default")
      (node (ref "SW1") (pin "2") (pintype "passive"))
      (node (ref "X1") (pin "1") (pinfunction "1_1") (pintype "passive"))
    )
    (net (code "127") (name "Net-(SW1-Pad5)") (class "Default")
      (node (ref "SW1") (pin "5") (pintype "passive"))
      (node (ref "X3") (pin "1") (pintype "passive"))
    )
    (net (code "128") (name "Net-(U1-Pad10)") (class "Default")
      (node (ref "U1") (pin "10") (pintype "input"))
      (node (ref "U1") (pin "11") (pintype "output"))
      (node (ref "U1") (pin "9") (pintype "input"))
    )
    (net (code "129") (name "Net-(U2-AUDIO_L)") (class "Default")
      (node (ref "R41") (pin "1") (pintype "passive"))
      (node (ref "U2") (pin "1") (pinfunction "AUDIO_L_1") (pintype "passive"))
    )
    (net (code "130") (name "Net-(U2-B2)") (class "Default")
      (node (ref "R20") (pin "1") (pintype "passive"))
      (node (ref "U2") (pin "35") (pinfunction "B2_35") (pintype "passive"))
    )
    (net (code "131") (name "Net-(U2-B3)") (class "Default")
      (node (ref "R24") (pin "1") (pintype "passive"))
      (node (ref "U2") (pin "34") (pinfunction "B3_34") (pintype "passive"))
    )
    (net (code "132") (name "Net-(U2-B4)") (class "Default")
      (node (ref "R25") (pin "1") (pintype "passive"))
      (node (ref "U2") (pin "33") (pinfunction "B4_33") (pintype "passive"))
    )
    (net (code "133") (name "Net-(U2-B5)") (class "Default")
      (node (ref "R26") (pin "1") (pintype "passive"))
      (node (ref "U2") (pin "32") (pinfunction "B5_32") (pintype "passive"))
    )
    (net (code "134") (name "Net-(U2-B6)") (class "Default")
      (node (ref "R29") (pin "1") (pintype "passive"))
      (node (ref "U2") (pin "31") (pinfunction "B6_31") (pintype "passive"))
    )
    (net (code "135") (name "Net-(U2-B7)") (class "Default")
      (node (ref "R31") (pin "1") (pintype "passive"))
      (node (ref "U2") (pin "30") (pinfunction "B7_30") (pintype "passive"))
    )
    (net (code "136") (name "Net-(U2-BACKLIGHT)") (class "Default")
      (node (ref "U2") (pin "24") (pinfunction "BACKLIGHT_24") (pintype "passive"))
      (node (ref "X4") (pin "5") (pinfunction "5_5") (pintype "passive"))
    )
    (net (code "137") (name "Net-(U2-DE)") (class "Default")
      (node (ref "U2") (pin "25") (pinfunction "DE_25") (pintype "passive"))
      (node (ref "X4") (pin "4") (pinfunction "4_4") (pintype "passive"))
    )
    (net (code "138") (name "Net-(U2-DISP)") (class "Default")
      (node (ref "U2") (pin "28") (pinfunction "DISP_28") (pintype "passive"))
      (node (ref "X4") (pin "3") (pinfunction "3_3") (pintype "passive"))
    )
    (net (code "139") (name "Net-(U2-G2)") (class "Default")
      (node (ref "R13") (pin "1") (pintype "passive"))
      (node (ref "U2") (pin "42") (pinfunction "G2_42") (pintype "passive"))
    )
    (net (code "140") (name "Net-(U2-G3)") (class "Default")
      (node (ref "R14") (pin "1") (pintype "passive"))
      (node (ref "U2") (pin "41") (pinfunction "G3_41") (pintype "passive"))
    )
    (net (code "141") (name "Net-(U2-G4)") (class "Default")
      (node (ref "R16") (pin "1") (pintype "passive"))
      (node (ref "U2") (pin "40") (pinfunction "G4_40") (pintype "passive"))
    )
    (net (code "142") (name "Net-(U2-G5)") (class "Default")
      (node (ref "R17") (pin "1") (pintype "passive"))
      (node (ref "U2") (pin "39") (pinfunction "G5_39") (pintype "passive"))
    )
    (net (code "143") (name "Net-(U2-G6)") (class "Default")
      (node (ref "R18") (pin "1") (pintype "passive"))
      (node (ref "U2") (pin "38") (pinfunction "G6_38") (pintype "passive"))
    )
    (net (code "144") (name "Net-(U2-G7)") (class "Default")
      (node (ref "R19") (pin "1") (pintype "passive"))
      (node (ref "U2") (pin "37") (pinfunction "G7_37") (pintype "passive"))
    )
    (net (code "145") (name "Net-(U2-HSYNC)") (class "Default")
      (node (ref "R37") (pin "1") (pintype "passive"))
      (node (ref "U2") (pin "27") (pinfunction "HSYNC_27") (pintype "passive"))
    )
    (net (code "146") (name "Net-(U2-PCLK)") (class "Default")
      (node (ref "U2") (pin "29") (pinfunction "PCLK_29") (pintype "passive"))
      (node (ref "X4") (pin "2") (pinfunction "2_2") (pintype "passive"))
    )
    (net (code "147") (name "Net-(U2-PD_N)") (class "Default")
      (node (ref "C11") (pin "1") (pintype "passive"))
      (node (ref "R12") (pin "2") (pintype "passive"))
      (node (ref "U2") (pin "12") (pinfunction "PD_N_12") (pintype "passive"))
    )
    (net (code "148") (name "Net-(U2-R2)") (class "Default")
      (node (ref "R5") (pin "1") (pintype "passive"))
      (node (ref "U2") (pin "48") (pinfunction "R2_48") (pintype "passive"))
    )
    (net (code "149") (name "Net-(U2-R3)") (class "Default")
      (node (ref "R6") (pin "1") (pintype "passive"))
      (node (ref "U2") (pin "47") (pinfunction "R3_47") (pintype "passive"))
    )
    (net (code "150") (name "Net-(U2-R4)") (class "Default")
      (node (ref "R8") (pin "1") (pintype "passive"))
      (node (ref "U2") (pin "46") (pinfunction "R4_46") (pintype "passive"))
    )
    (net (code "151") (name "Net-(U2-R5)") (class "Default")
      (node (ref "R9") (pin "1") (pintype "passive"))
      (node (ref "U2") (pin "45") (pinfunction "R5_45") (pintype "passive"))
    )
    (net (code "152") (name "Net-(U2-R6)") (class "Default")
      (node (ref "R10") (pin "1") (pintype "passive"))
      (node (ref "U2") (pin "44") (pinfunction "R6_44") (pintype "passive"))
    )
    (net (code "153") (name "Net-(U2-R7)") (class "Default")
      (node (ref "R11") (pin "1") (pintype "passive"))
      (node (ref "U2") (pin "43") (pinfunction "R7_43") (pintype "passive"))
    )
    (net (code "154") (name "Net-(U2-VCC1V2)") (class "Default")
      (node (ref "C10") (pin "1") (pintype "passive"))
      (node (ref "U2") (pin "17") (pinfunction "VCC1V2_17") (pintype "passive"))
    )
    (net (code "155") (name "Net-(U2-VSYNC)") (class "Default")
      (node (ref "R38") (pin "1") (pintype "passive"))
      (node (ref "U2") (pin "26") (pinfunction "VSYNC_26") (pintype "passive"))
    )
    (net (code "156") (name "Net-(U2-X+)") (class "Default")
      (node (ref "U2") (pin "19") (pinfunction "X+_19") (pintype "passive"))
      (node (ref "X8") (pin "4") (pinfunction "4_4") (pintype "passive"))
    )
    (net (code "157") (name "Net-(U2-X-)") (class "Default")
      (node (ref "U2") (pin "21") (pinfunction "X-_21") (pintype "passive"))
      (node (ref "X8") (pin "2") (pinfunction "2_2") (pintype "passive"))
    )
    (net (code "158") (name "Net-(U2-X1{slash}CLK)") (class "Default")
      (node (ref "C22") (pin "1") (pintype "passive"))
      (node (ref "U2") (pin "13") (pinfunction "X1/CLK_13") (pintype "passive"))
      (node (ref "Y1") (pin "2") (pintype "passive"))
    )
    (net (code "159") (name "Net-(U2-X2)") (class "Default")
      (node (ref "C24") (pin "1") (pintype "passive"))
      (node (ref "U2") (pin "14") (pinfunction "X2_14") (pintype "passive"))
      (node (ref "Y1") (pin "1") (pintype "passive"))
    )
    (net (code "160") (name "Net-(U2-Y+)") (class "Default")
      (node (ref "U2") (pin "20") (pinfunction "Y+_20") (pintype "passive"))
      (node (ref "X8") (pin "3") (pinfunction "3_3") (pintype "passive"))
    )
    (net (code "161") (name "Net-(U2-Y-)") (class "Default")
      (node (ref "U2") (pin "22") (pinfunction "Y-_22") (pintype "passive"))
      (node (ref "X8") (pin "1") (pinfunction "1_1") (pintype "passive"))
    )
    (net (code "162") (name "Net-(U3-C1+)") (class "Default")
      (node (ref "C16") (pin "1") (pintype "passive"))
      (node (ref "U3") (pin "1") (pinfunction "C1+_1") (pintype "passive"))
    )
    (net (code "163") (name "Net-(U3-C1-)") (class "Default")
      (node (ref "C16") (pin "2") (pintype "passive"))
      (node (ref "U3") (pin "3") (pinfunction "C1-_3") (pintype "passive"))
    )
    (net (code "164") (name "Net-(U3-C2+)") (class "Default")
      (node (ref "C19") (pin "2") (pintype "passive"))
      (node (ref "U3") (pin "4") (pinfunction "C2+_4") (pintype "passive"))
    )
    (net (code "165") (name "Net-(U3-C2-)") (class "Default")
      (node (ref "C19") (pin "1") (pintype "passive"))
      (node (ref "U3") (pin "5") (pinfunction "C2-_5") (pintype "passive"))
    )
    (net (code "166") (name "Net-(U3-R1IN)") (class "Default")
      (node (ref "R33") (pin "1") (pintype "passive"))
      (node (ref "U3") (pin "13") (pinfunction "R1IN_13") (pintype "passive"))
    )
    (net (code "167") (name "Net-(U3-R2IN)") (class "Default")
      (node (ref "R34") (pin "1") (pintype "passive"))
      (node (ref "U3") (pin "8") (pinfunction "R2IN_8") (pintype "passive"))
    )
    (net (code "168") (name "Net-(U3-T1OUT)") (class "Default")
      (node (ref "R28") (pin "1") (pintype "passive"))
      (node (ref "U3") (pin "14") (pinfunction "T1OUT_14") (pintype "passive"))
    )
    (net (code "169") (name "Net-(U3-T2OUT)") (class "Default")
      (node (ref "R30") (pin "1") (pintype "passive"))
      (node (ref "U3") (pin "7") (pinfunction "T2OUT_7") (pintype "passive"))
    )
    (net (code "170") (name "Net-(U3-Vs+)") (class "Default")
      (node (ref "C20") (pin "2") (pintype "passive"))
      (node (ref "U3") (pin "2") (pinfunction "Vs+_2") (pintype "passive"))
    )
    (net (code "171") (name "Net-(U3-Vs-)") (class "Default")
      (node (ref "C21") (pin "2") (pintype "passive"))
      (node (ref "U3") (pin "6") (pinfunction "Vs-_6") (pintype "passive"))
    )
    (net (code "172") (name "Net-(U5-AVDD)") (class "Default")
      (node (ref "C35") (pin "2") (pintype "passive"))
      (node (ref "L1") (pin "1") (pintype "passive"))
      (node (ref "U5") (pin "31") (pinfunction "AVDD_31") (pintype "passive"))
    )
    (net (code "173") (name "Net-(U5-VREF)") (class "Default")
      (node (ref "C40") (pin "2") (pintype "passive"))
      (node (ref "U5") (pin "44") (pinfunction "VREF_44") (pintype "passive"))
    )
    (net (code "174") (name "Net-(U5-XIN)") (class "Default")
      (node (ref "C41") (pin "1") (pintype "passive"))
      (node (ref "U5") (pin "24") (pinfunction "XIN_24") (pintype "passive"))
      (node (ref "Y2") (pin "1") (pintype "passive"))
    )
    (net (code "175") (name "Net-(U5-XOUT)") (class "Default")
      (node (ref "R44") (pin "1") (pintype "passive"))
      (node (ref "U5") (pin "23") (pinfunction "XOUT_23") (pintype "passive"))
    )
    (net (code "176") (name "Net-(U6-~MR)") (class "Default")
      (node (ref "SW2") (pin "2") (pintype "passive"))
      (node (ref "U6") (pin "4") (pinfunction "~MR_4") (pintype "input"))
    )
    (net (code "177") (name "Net-(U9-Vbat)") (class "Default")
      (node (ref "C48") (pin "1") (pintype "passive"))
      (node (ref "D4") (pin "1") (pintype "passive"))
      (node (ref "U9") (pin "7") (pinfunction "Vbat_7") (pintype "power_in"))
    )
    (net (code "178") (name "Net-(U9-X1)") (class "Default")
      (node (ref "U9") (pin "1") (pinfunction "X1_1") (pintype "passive"))
      (node (ref "Y3") (pin "2") (pintype "passive"))
    )
    (net (code "179") (name "Net-(U9-X2)") (class "Default")
      (node (ref "U9") (pin "2") (pinfunction "X2_2") (pintype "passive"))
      (node (ref "Y3") (pin "1") (pintype "passive"))
    )
    (net (code "180") (name "unconnected-(J2-Pad4)") (class "Default")
      (node (ref "J2") (pin "4") (pinfunction "4_4") (pintype "passive+no_connect"))
    )
    (net (code "181") (name "unconnected-(J2-Pad11)") (class "Default")
      (node (ref "J2") (pin "11") (pinfunction "11_11") (pintype "passive+no_connect"))
    )
    (net (code "182") (name "unconnected-(J2-Pad12)") (class "Default")
      (node (ref "J2") (pin "12") (pinfunction "12_12") (pintype "passive+no_connect"))
    )
    (net (code "183") (name "unconnected-(J2-Pad15)") (class "Default")
      (node (ref "J2") (pin "15") (pinfunction "15_15") (pintype "passive+no_connect"))
    )
    (net (code "184") (name "unconnected-(J3-Pad1)") (class "Default")
      (node (ref "J3") (pin "1") (pinfunction "1_1") (pintype "passive+no_connect"))
    )
    (net (code "185") (name "unconnected-(J3-Pad6)") (class "Default")
      (node (ref "J3") (pin "6") (pinfunction "6_6") (pintype "passive+no_connect"))
    )
    (net (code "186") (name "unconnected-(J3-Pad9)") (class "Default")
      (node (ref "J3") (pin "9") (pinfunction "9_9") (pintype "passive+no_connect"))
    )
    (net (code "187") (name "unconnected-(MOD1-NC-Pad6)") (class "Default")
      (node (ref "MOD1") (pin "6") (pinfunction "NC_6") (pintype "power_in+no_connect"))
    )
    (net (code "188") (name "unconnected-(MOD2-REM-Pad3)") (class "Default")
      (node (ref "MOD2") (pin "3") (pinfunction "REM_3") (pintype "passive+no_connect"))
    )
    (net (code "189") (name "unconnected-(SW1-Pad3)") (class "Default")
      (node (ref "SW1") (pin "3") (pintype "passive+no_connect"))
    )
    (net (code "190") (name "unconnected-(SW1-Pad6)") (class "Default")
      (node (ref "SW1") (pin "6") (pintype "passive+no_connect"))
    )
    (net (code "191") (name "unconnected-(U2-GPIO0{slash}I2C_SA2-Pad7)") (class "Default")
      (node (ref "U2") (pin "7") (pinfunction "GPIO0/I2C_SA2_7") (pintype "passive+no_connect"))
    )
    (net (code "192") (name "unconnected-(U2-GPIO1-Pad8)") (class "Default")
      (node (ref "U2") (pin "8") (pinfunction "GPIO1_8") (pintype "passive+no_connect"))
    )
    (net (code "193") (name "unconnected-(U6-RST-Pad3)") (class "Default")
      (node (ref "U6") (pin "3") (pinfunction "RST_3") (pintype "output+no_connect"))
    )
    (net (code "194") (name "unconnected-(U9-~IRQ{slash}Fout-Pad3)") (class "Default")
      (node (ref "U9") (pin "3") (pinfunction "~IRQ/Fout_3") (pintype "open_collector+no_connect"))
    )
    (net (code "195") (name "unconnected-(X9-Pad6)") (class "Default")
      (node (ref "X9") (pin "6") (pinfunction "6_6") (pintype "passive+no_connect"))
    )
    (net (code "196") (name "unconnected-(X10-DAT1-Pad8)") (class "Default")
      (node (ref "X10") (pin "8") (pinfunction "DAT1_8") (pintype "passive+no_connect"))
    )
    (net (code "197") (name "unconnected-(X10-DAT2-Pad9)") (class "Default")
      (node (ref "X10") (pin "9") (pinfunction "DAT2_9") (pintype "passive+no_connect"))
    )
    (net (code "198") (name "unconnected-(X11-DAT1-Pad8)") (class "Default")
      (node (ref "X11") (pin "8") (pinfunction "DAT1_8") (pintype "passive+no_connect"))
    )
    (net (code "199") (name "unconnected-(X11-DAT2-Pad9)") (class "Default")
      (node (ref "X11") (pin "9") (pinfunction "DAT2_9") (pintype "passive+no_connect"))
    )
    (net (code "200") (name "unconnected-(X12-DAT1-Pad8)") (class "Default")
      (node (ref "X12") (pin "8") (pinfunction "DAT1_8") (pintype "passive+no_connect"))
    )
    (net (code "201") (name "unconnected-(X12-DAT2-Pad1)") (class "Default")
      (node (ref "X12") (pin "1") (pinfunction "DAT2_1") (pintype "passive+no_connect"))
    )
  )
)
